# mainboard-gsm.net
KiCad netlist of a schematic drawn in EAGLE
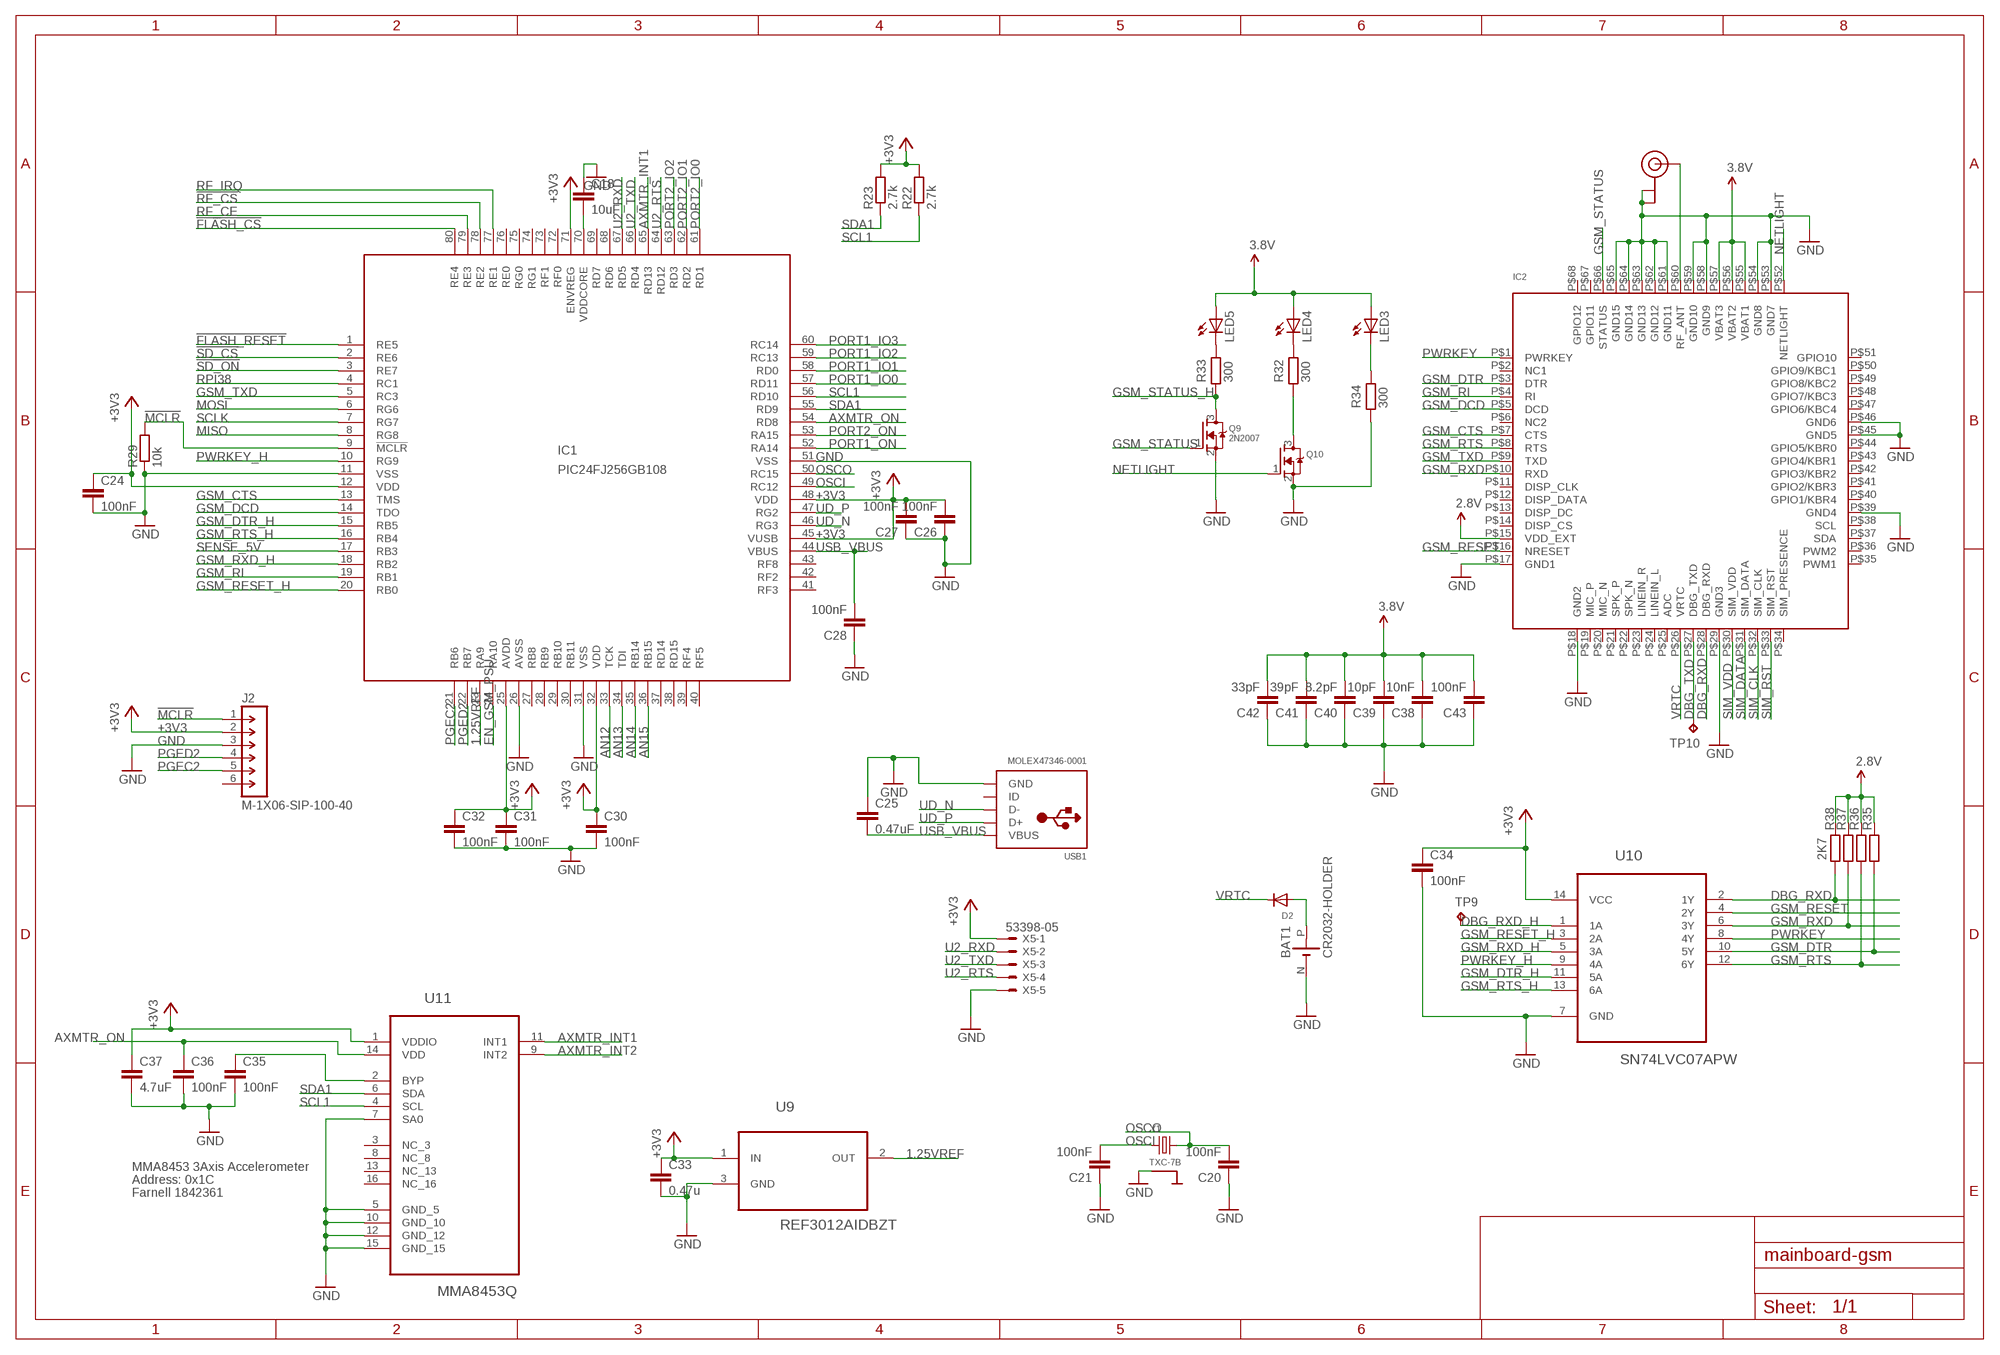
[diagram p0: schematic, sheet 1, part 1 of 3]
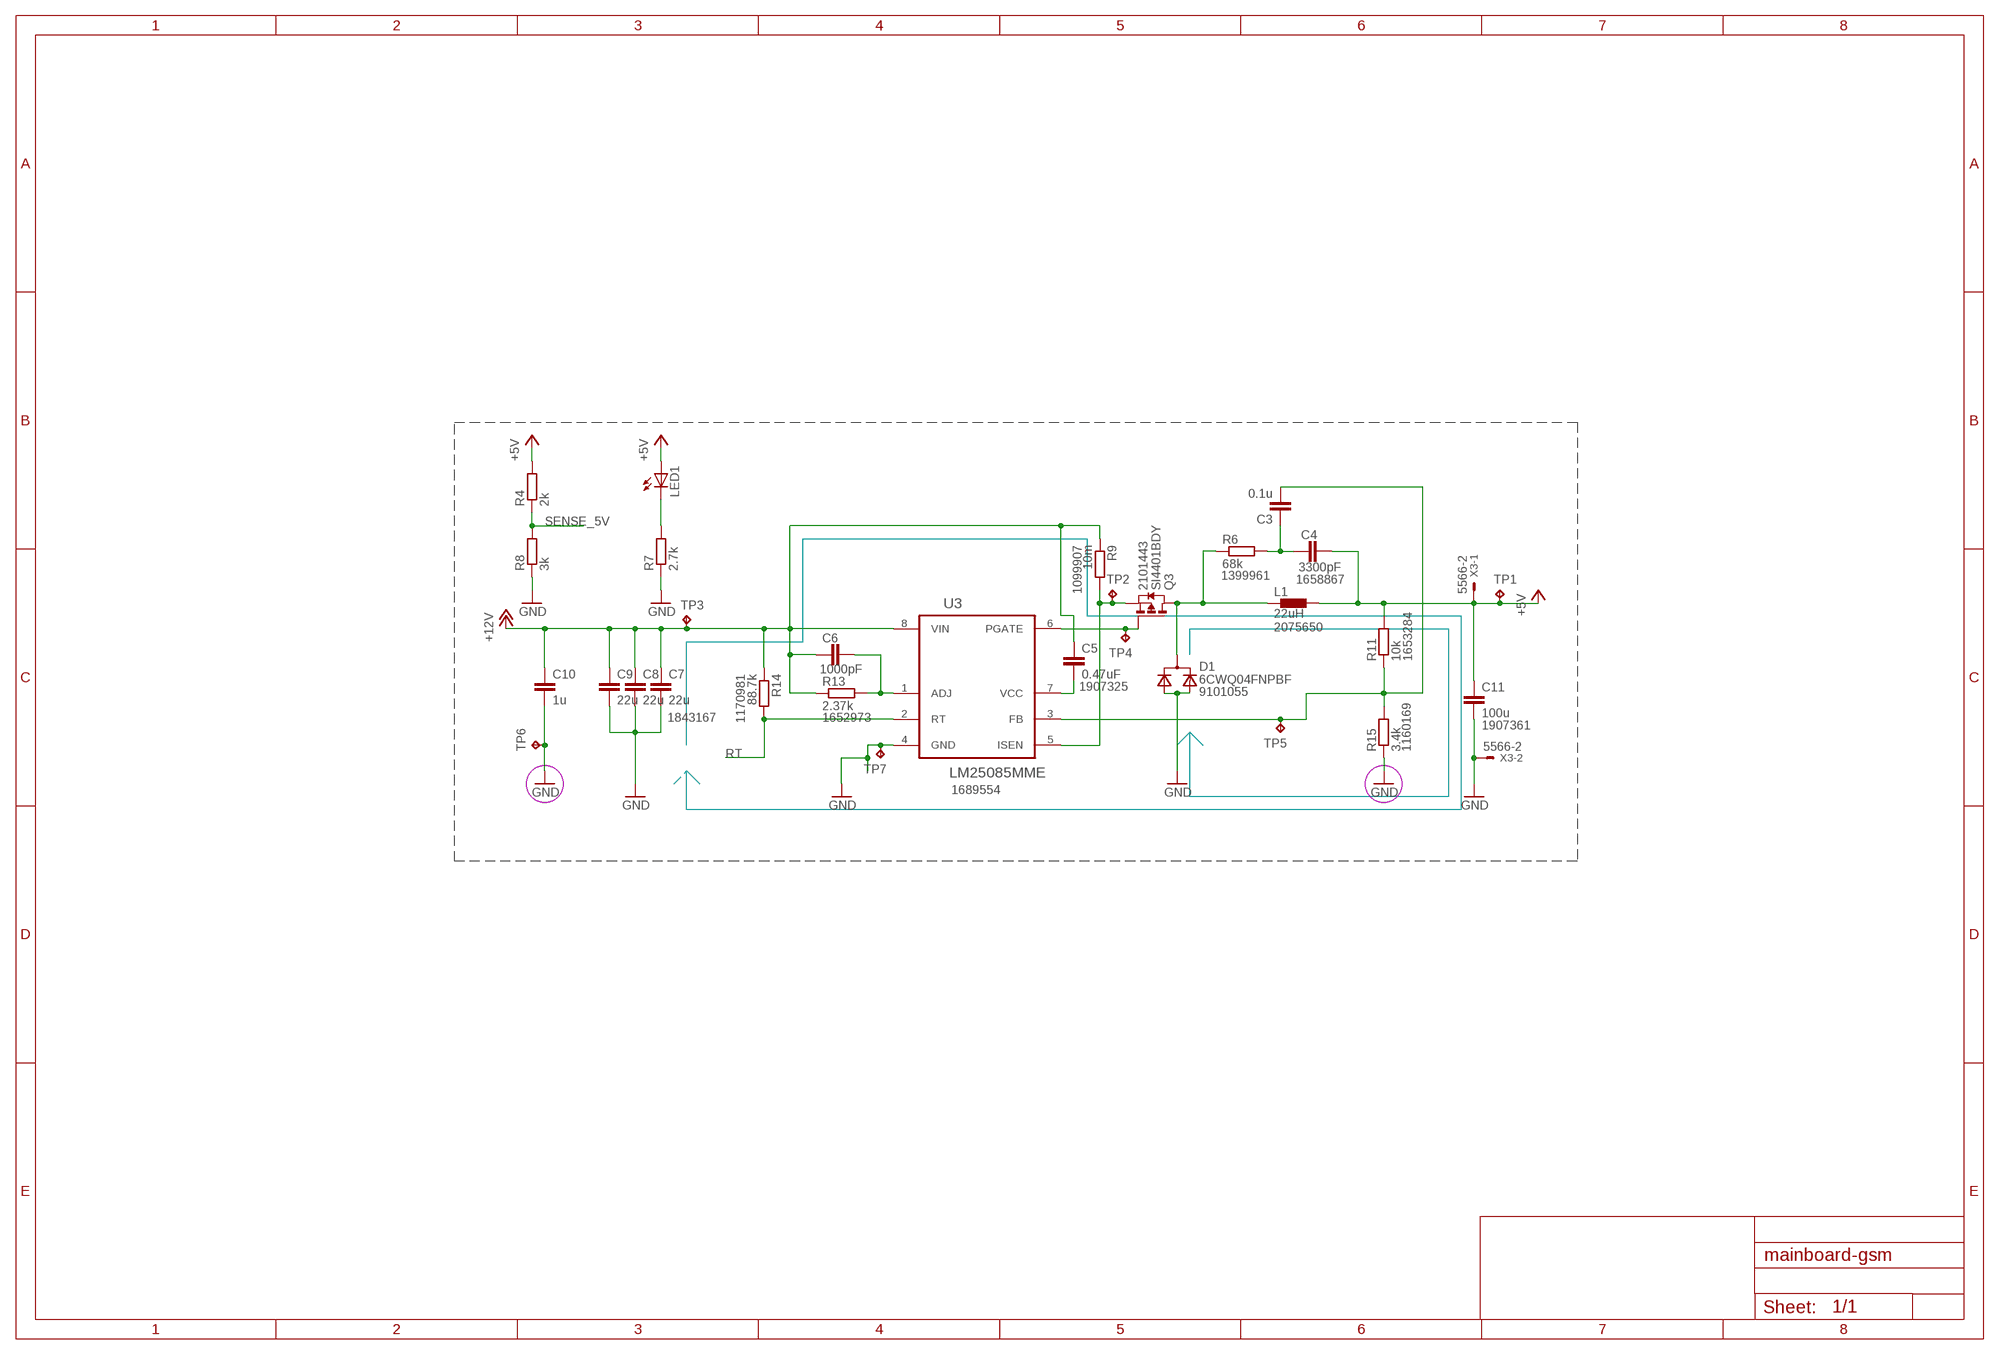
[diagram p1: schematic, sheet 1, part 2 of 3]
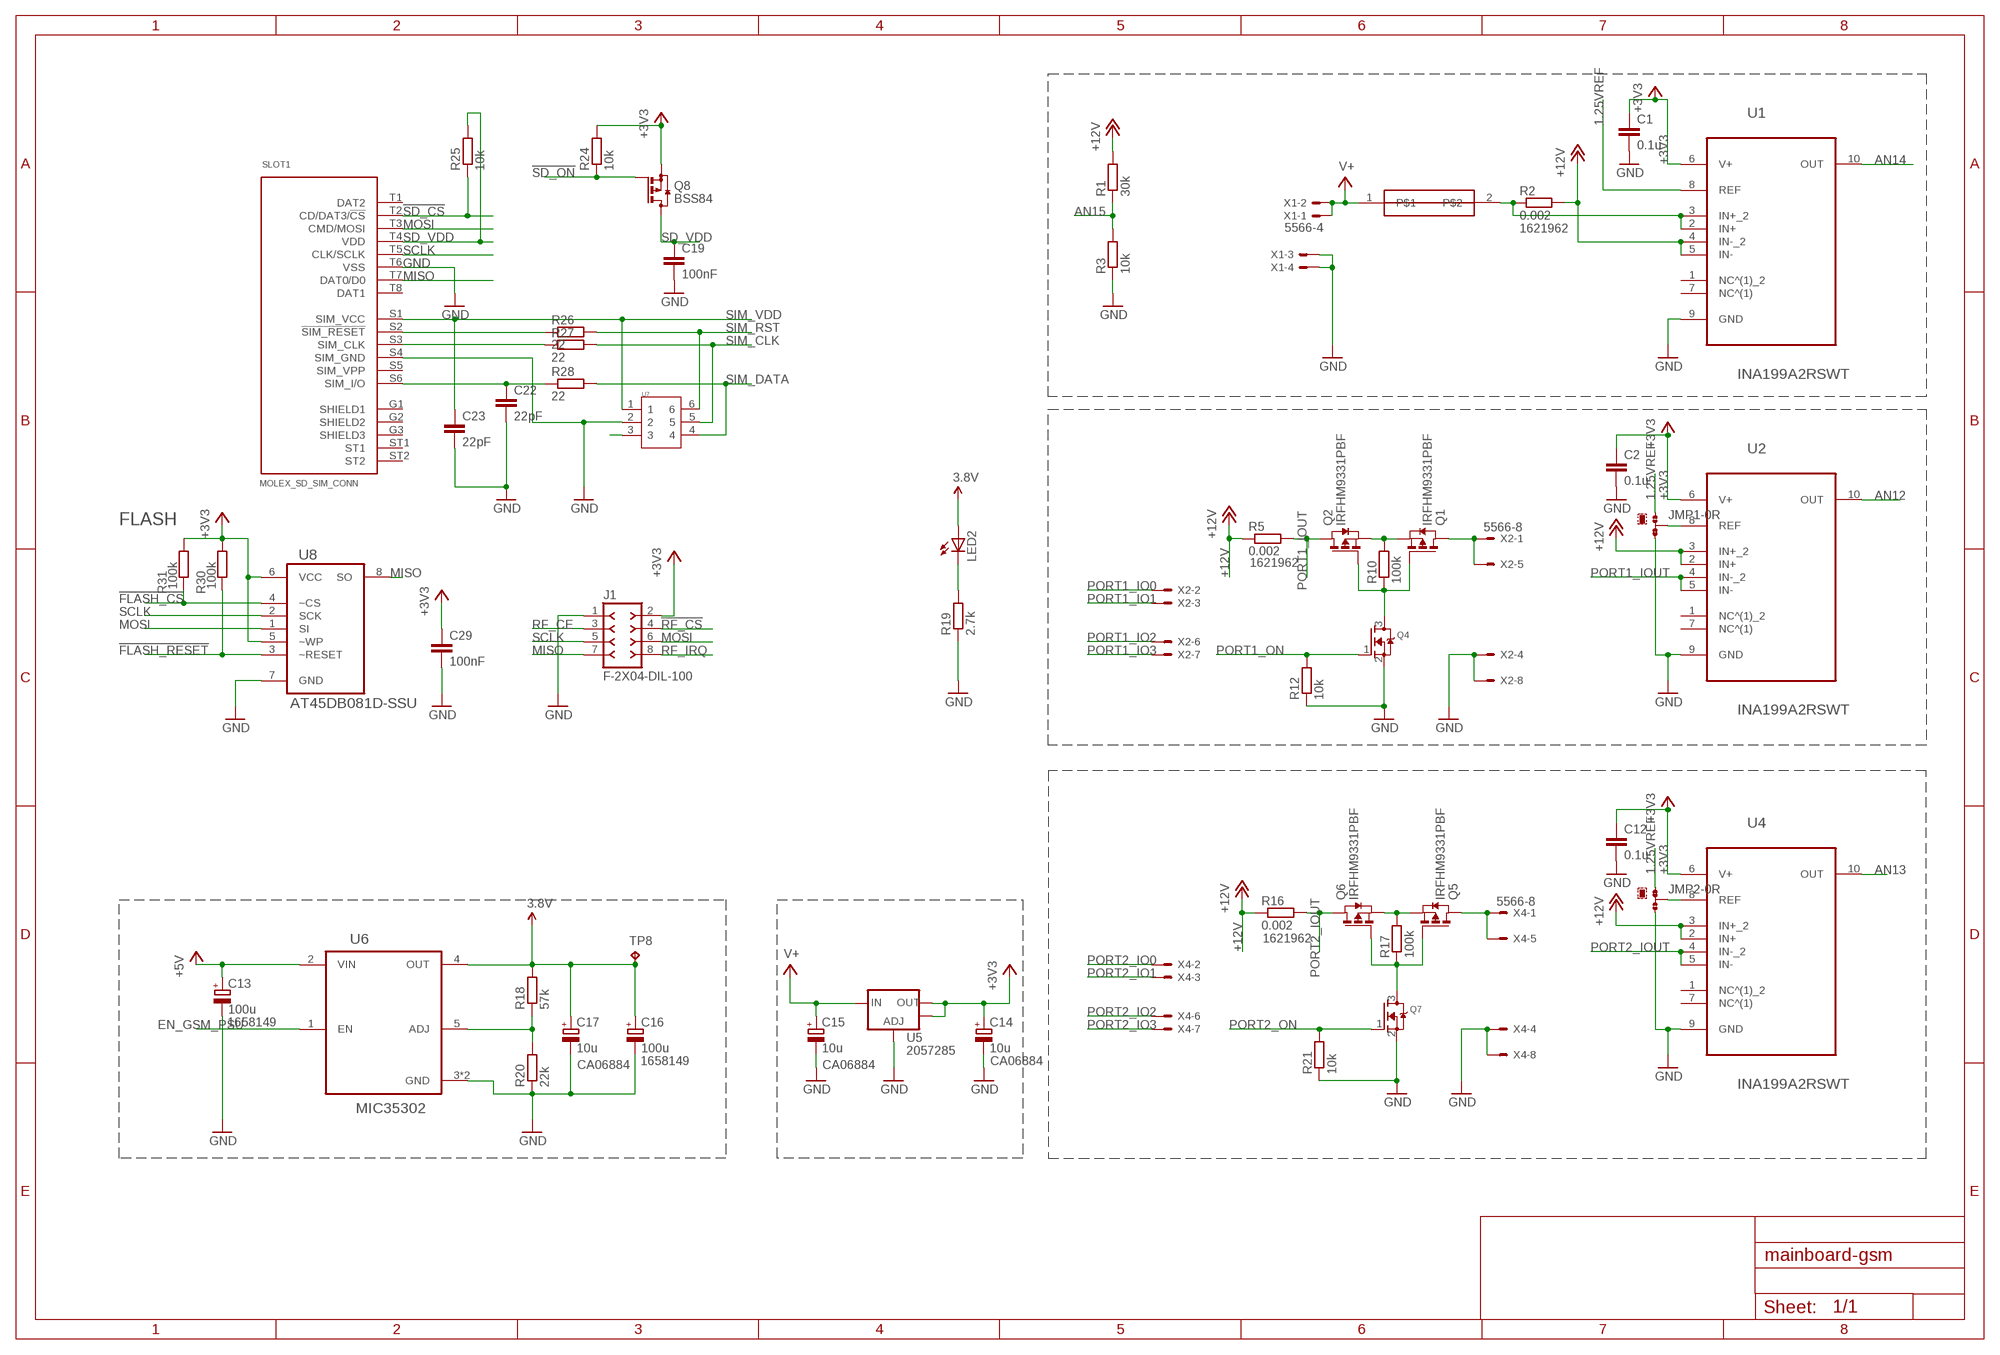
[diagram p2: schematic, sheet 1, part 3 of 3]

(export (version "E")
  (design (tool "Eeschema 10.0.6"))
  (components
    (comp (ref "ANT1")
      (value "U.FL")
      (footprint "eagle-import:U.FL")
      (libsource (lib "eagle-import") (part "U.FL"))
    )
    (comp (ref "BAT1")
      (value "CR2032-HOLDER")
      (footprint "eagle-import:CH28-2032L")
      (libsource (lib "eagle-import") (part "CR2032-HOLDER"))
    )
    (comp (ref "C1")
      (value "0.1u")
      (footprint "eagle-import:C0603")
      (libsource (lib "eagle-import") (part "C-EUC0603"))
    )
    (comp (ref "C2")
      (value "0.1u")
      (footprint "eagle-import:C0603")
      (libsource (lib "eagle-import") (part "C-EUC0603"))
    )
    (comp (ref "C3")
      (value "0.1u")
      (footprint "eagle-import:C0603")
      (libsource (lib "eagle-import") (part "C-EUC0603"))
    )
    (comp (ref "C4")
      (value "3300pF")
      (footprint "eagle-import:C0603")
      (fields (field (name "FARNELL") "1658867"))
      (libsource (lib "eagle-import") (part "C-EUC0603"))
    )
    (comp (ref "C5")
      (value "0.47uF")
      (footprint "eagle-import:C0805")
      (fields (field (name "FARNELL") "1907325"))
      (libsource (lib "eagle-import") (part "C-EUC0805"))
    )
    (comp (ref "C6")
      (value "1000pF")
      (footprint "eagle-import:C0603")
      (libsource (lib "eagle-import") (part "C-EUC0603"))
    )
    (comp (ref "C7")
      (value "22u")
      (footprint "eagle-import:C1812")
      (fields (field (name "FARNELL") "1843167"))
      (libsource (lib "eagle-import") (part "C-EUC1812"))
    )
    (comp (ref "C8")
      (value "22u")
      (footprint "eagle-import:C1812")
      (libsource (lib "eagle-import") (part "C-EUC1812"))
    )
    (comp (ref "C9")
      (value "22u")
      (footprint "eagle-import:C1812")
      (libsource (lib "eagle-import") (part "C-EUC1812"))
    )
    (comp (ref "C10")
      (value "1u")
      (footprint "eagle-import:C0805")
      (libsource (lib "eagle-import") (part "C-EUC0805"))
    )
    (comp (ref "C11")
      (value "100u")
      (footprint "eagle-import:C1210")
      (fields (field (name "FARNELL") "1907361"))
      (libsource (lib "eagle-import") (part "C-EUC1210"))
    )
    (comp (ref "C12")
      (value "0.1u")
      (footprint "eagle-import:C0603")
      (libsource (lib "eagle-import") (part "C-EUC0603"))
    )
    (comp (ref "C13")
      (value "100u")
      (footprint "eagle-import:B_3528-21R")
      (fields (field (name "FARNELL") "1658149"))
      (libsource (lib "eagle-import") (part "CPOL-EUB/3528-21R"))
    )
    (comp (ref "C14")
      (value "10u")
      (footprint "eagle-import:D_7343-31R")
      (fields (field (name "FARNELL") "CA06884"))
      (libsource (lib "eagle-import") (part "CPOL-EUD/7343-31R"))
    )
    (comp (ref "C15")
      (value "10u")
      (footprint "eagle-import:D_7343-31R")
      (fields (field (name "FARNELL") "CA06884"))
      (libsource (lib "eagle-import") (part "CPOL-EUD/7343-31R"))
    )
    (comp (ref "C16")
      (value "100u")
      (footprint "eagle-import:B_3528-21R")
      (fields (field (name "FARNELL") "1658149"))
      (libsource (lib "eagle-import") (part "CPOL-EUB/3528-21R"))
    )
    (comp (ref "C17")
      (value "10u")
      (footprint "eagle-import:D_7343-31R")
      (fields (field (name "FARNELL") "CA06884"))
      (libsource (lib "eagle-import") (part "CPOL-EUD/7343-31R"))
    )
    (comp (ref "C18")
      (value "10uF")
      (footprint "eagle-import:C0805")
      (libsource (lib "eagle-import") (part "C-EUC0805"))
    )
    (comp (ref "C19")
      (value "100nF")
      (footprint "eagle-import:C0603")
      (libsource (lib "eagle-import") (part "C-EUC0603"))
    )
    (comp (ref "C20")
      (value "100nF")
      (footprint "eagle-import:C0603")
      (libsource (lib "eagle-import") (part "C-EUC0603"))
    )
    (comp (ref "C21")
      (value "100nF")
      (footprint "eagle-import:C0603")
      (libsource (lib "eagle-import") (part "C-EUC0603"))
    )
    (comp (ref "C22")
      (value "22pF")
      (footprint "eagle-import:C0603")
      (libsource (lib "eagle-import") (part "C-EUC0603"))
    )
    (comp (ref "C23")
      (value "22pF")
      (footprint "eagle-import:C0603")
      (libsource (lib "eagle-import") (part "C-EUC0603"))
    )
    (comp (ref "C24")
      (value "100nF")
      (footprint "eagle-import:C0603")
      (libsource (lib "eagle-import") (part "C-EUC0603"))
    )
    (comp (ref "C25")
      (value "0.47uF")
      (footprint "eagle-import:C1206")
      (libsource (lib "eagle-import") (part "C-EUC1206"))
    )
    (comp (ref "C26")
      (value "100nF")
      (footprint "eagle-import:C0603")
      (libsource (lib "eagle-import") (part "C-EUC0603"))
    )
    (comp (ref "C27")
      (value "100nF")
      (footprint "eagle-import:C0603")
      (libsource (lib "eagle-import") (part "C-EUC0603"))
    )
    (comp (ref "C28")
      (value "100nF")
      (footprint "eagle-import:C0603")
      (libsource (lib "eagle-import") (part "C-EUC0603"))
    )
    (comp (ref "C29")
      (value "100nF")
      (footprint "eagle-import:C0603")
      (libsource (lib "eagle-import") (part "C-EUC0603"))
    )
    (comp (ref "C30")
      (value "100nF")
      (footprint "eagle-import:C0603")
      (libsource (lib "eagle-import") (part "C-EUC0603"))
    )
    (comp (ref "C31")
      (value "100nF")
      (footprint "eagle-import:C0603")
      (libsource (lib "eagle-import") (part "C-EUC0603"))
    )
    (comp (ref "C32")
      (value "100nF")
      (footprint "eagle-import:C0603")
      (libsource (lib "eagle-import") (part "C-EUC0603"))
    )
    (comp (ref "C33")
      (value "0.47u")
      (footprint "eagle-import:C0805")
      (libsource (lib "eagle-import") (part "C-EUC0805"))
    )
    (comp (ref "C34")
      (value "100nF")
      (footprint "eagle-import:C0603")
      (libsource (lib "eagle-import") (part "C-EUC0603"))
    )
    (comp (ref "C35")
      (value "100nF")
      (footprint "eagle-import:C0603")
      (libsource (lib "eagle-import") (part "C-EUC0603"))
    )
    (comp (ref "C36")
      (value "100nF")
      (footprint "eagle-import:C0603")
      (libsource (lib "eagle-import") (part "C-EUC0603"))
    )
    (comp (ref "C37")
      (value "4.7uF")
      (footprint "eagle-import:C0805")
      (libsource (lib "eagle-import") (part "C-EUC0805"))
    )
    (comp (ref "C38")
      (value "10nF")
      (footprint "eagle-import:C0603")
      (libsource (lib "eagle-import") (part "C-EUC0603"))
    )
    (comp (ref "C39")
      (value "10pF")
      (footprint "eagle-import:C0603")
      (libsource (lib "eagle-import") (part "C-EUC0603"))
    )
    (comp (ref "C40")
      (value "8.2pF")
      (footprint "eagle-import:C0603")
      (libsource (lib "eagle-import") (part "C-EUC0603"))
    )
    (comp (ref "C41")
      (value "39pF")
      (footprint "eagle-import:C0603")
      (libsource (lib "eagle-import") (part "C-EUC0603"))
    )
    (comp (ref "C42")
      (value "33pF")
      (footprint "eagle-import:C0603")
      (libsource (lib "eagle-import") (part "C-EUC0603"))
    )
    (comp (ref "C43")
      (value "100nF")
      (footprint "eagle-import:C0603")
      (libsource (lib "eagle-import") (part "C-EUC0603"))
    )
    (comp (ref "CONN1")
      (value "MINIBLADE_SOCKET")
      (footprint "eagle-import:LTF153008")
      (libsource (lib "eagle-import") (part "MINIBLADE_SOCKET"))
    )
    (comp (ref "D1")
      (value "6CWQ04FNPBF")
      (footprint "eagle-import:TO252-AA")
      (fields (field (name "FARNELL") "9101055"))
      (libsource (lib "eagle-import") (part "6CWQ04FNPBF"))
    )
    (comp (ref "D2")
      (value "DIODESOD-123")
      (footprint "eagle-import:SOD-123")
      (libsource (lib "eagle-import") (part "DIODESOD-123"))
    )
    (comp (ref "IC1")
      (value "PIC24FJ256GB108")
      (footprint "eagle-import:TQFP80-12X12")
      (fields
        (field (name "MPN") "PIC24FJ256GB108-I/PT")
        (field (name "MPN_1") "PIC24FJ256GB108-I/PT")
        (field (name "OC_FARNELL") "1576869")
        (field (name "OC_NEWARK") "54M5131")
      )
      (libsource (lib "eagle-import") (part "PIC24FJ256GB108"))
    )
    (comp (ref "IC2")
      (value "SIM900_LITERAL")
      (footprint "eagle-import:SIM900_SMT")
      (libsource (lib "eagle-import") (part "SIM900_LITERAL"))
    )
    (comp (ref "J1")
      (value "F-2X04-DIL-100")
      (footprint "eagle-import:DIL-100-2X04")
      (libsource (lib "eagle-import") (part "F-2X04-DIL-100"))
    )
    (comp (ref "J2")
      (value "M-1X06-SIP-100-40")
      (footprint "eagle-import:SIP-100-06-40")
      (libsource (lib "eagle-import") (part "M-1X06-SIP-100-40"))
    )
    (comp (ref "JMP1")
      (value "0R-JUMPA")
      (footprint "eagle-import:A0R-JMP")
      (libsource (lib "eagle-import") (part "0R-JUMPA"))
    )
    (comp (ref "JMP2")
      (value "0R-JUMPA")
      (footprint "eagle-import:A0R-JMP")
      (libsource (lib "eagle-import") (part "0R-JUMPA"))
    )
    (comp (ref "L1")
      (value "22uH")
      (footprint "eagle-import:HC9-XXX-R")
      (fields (field (name "FARNELL") "2075650"))
      (libsource (lib "eagle-import") (part "HC9-XXX-R"))
    )
    (comp (ref "LED1")
      (value "LEDCHIPLED_0805")
      (footprint "eagle-import:CHIPLED_0805")
      (libsource (lib "eagle-import") (part "LEDCHIPLED_0805"))
    )
    (comp (ref "LED2")
      (value "LEDCHIPLED_0805")
      (footprint "eagle-import:CHIPLED_0805")
      (libsource (lib "eagle-import") (part "LEDCHIPLED_0805"))
    )
    (comp (ref "LED3")
      (value "LEDCHIPLED_0805")
      (footprint "eagle-import:CHIPLED_0805")
      (libsource (lib "eagle-import") (part "LEDCHIPLED_0805"))
    )
    (comp (ref "LED4")
      (value "LEDCHIPLED_0805")
      (footprint "eagle-import:CHIPLED_0805")
      (libsource (lib "eagle-import") (part "LEDCHIPLED_0805"))
    )
    (comp (ref "LED5")
      (value "LEDCHIPLED_0805")
      (footprint "eagle-import:CHIPLED_0805")
      (libsource (lib "eagle-import") (part "LEDCHIPLED_0805"))
    )
    (comp (ref "Q1")
      (value "IRFHM9331PBF")
      (footprint "eagle-import:IR_PQFN_FET")
      (libsource (lib "eagle-import") (part "IRFHM9331PBF"))
    )
    (comp (ref "Q2")
      (value "IRFHM9331PBF")
      (footprint "eagle-import:IR_PQFN_FET")
      (libsource (lib "eagle-import") (part "IRFHM9331PBF"))
    )
    (comp (ref "Q3")
      (value "SI4401BDY")
      (footprint "eagle-import:SO8-FET")
      (fields (field (name "FARNELL") "2101443"))
      (libsource (lib "eagle-import") (part "SI4401BDY"))
    )
    (comp (ref "Q4")
      (value "MOSFET-NREFLOW")
      (footprint "eagle-import:SOT23")
      (libsource (lib "eagle-import") (part "MOSFET-NREFLOW"))
    )
    (comp (ref "Q5")
      (value "IRFHM9331PBF")
      (footprint "eagle-import:IR_PQFN_FET")
      (libsource (lib "eagle-import") (part "IRFHM9331PBF"))
    )
    (comp (ref "Q6")
      (value "IRFHM9331PBF")
      (footprint "eagle-import:IR_PQFN_FET")
      (libsource (lib "eagle-import") (part "IRFHM9331PBF"))
    )
    (comp (ref "Q7")
      (value "MOSFET-NREFLOW")
      (footprint "eagle-import:SOT23")
      (libsource (lib "eagle-import") (part "MOSFET-NREFLOW"))
    )
    (comp (ref "Q8")
      (value "BSS84")
      (footprint "eagle-import:SOT23")
      (libsource (lib "eagle-import") (part "BSS84"))
    )
    (comp (ref "Q9")
      (value "2N2007")
      (footprint "eagle-import:SOT23")
      (libsource (lib "eagle-import") (part "MOSFET-NREFLOW"))
    )
    (comp (ref "Q10")
      (value "MOSFET-NREFLOW")
      (footprint "eagle-import:SOT23")
      (libsource (lib "eagle-import") (part "MOSFET-NREFLOW"))
    )
    (comp (ref "R1")
      (value "30k")
      (footprint "eagle-import:R0805")
      (libsource (lib "eagle-import") (part "R-EU_R0805"))
    )
    (comp (ref "R2")
      (value "0.002")
      (footprint "eagle-import:R1206")
      (fields (field (name "FARNELL") "1621962"))
      (libsource (lib "eagle-import") (part "R-EU_R1206"))
    )
    (comp (ref "R3")
      (value "10k")
      (footprint "eagle-import:R0805")
      (libsource (lib "eagle-import") (part "R-EU_R0805"))
    )
    (comp (ref "R4")
      (value "2k")
      (footprint "eagle-import:R0805")
      (libsource (lib "eagle-import") (part "R-EU_R0805"))
    )
    (comp (ref "R5")
      (value "0.002")
      (footprint "eagle-import:R1206")
      (fields (field (name "FARNELL") "1621962"))
      (libsource (lib "eagle-import") (part "R-EU_R1206"))
    )
    (comp (ref "R6")
      (value "68k")
      (footprint "eagle-import:R0603")
      (fields (field (name "FARNELL") "1399961"))
      (libsource (lib "eagle-import") (part "R-EU_R0603"))
    )
    (comp (ref "R7")
      (value "2.7k")
      (footprint "eagle-import:R0805")
      (libsource (lib "eagle-import") (part "R-EU_R0805"))
    )
    (comp (ref "R8")
      (value "3k")
      (footprint "eagle-import:R0805")
      (libsource (lib "eagle-import") (part "R-EU_R0805"))
    )
    (comp (ref "R9")
      (value "10m")
      (footprint "eagle-import:R1206")
      (fields (field (name "FARNELL") "1099907"))
      (libsource (lib "eagle-import") (part "R-EU_R1206"))
    )
    (comp (ref "R10")
      (value "100k")
      (footprint "eagle-import:R0603")
      (libsource (lib "eagle-import") (part "R-EU_R0603"))
    )
    (comp (ref "R11")
      (value "10k")
      (footprint "eagle-import:R0805")
      (fields (field (name "FARNELL") "1653284"))
      (libsource (lib "eagle-import") (part "R-EU_R0805"))
    )
    (comp (ref "R12")
      (value "10k")
      (footprint "eagle-import:R0603")
      (libsource (lib "eagle-import") (part "R-EU_R0603"))
    )
    (comp (ref "R13")
      (value "2.37k")
      (footprint "eagle-import:R0805")
      (fields (field (name "FARNELL") "1652973"))
      (libsource (lib "eagle-import") (part "R-EU_R0805"))
    )
    (comp (ref "R14")
      (value "88.7k")
      (footprint "eagle-import:R0603")
      (fields (field (name "FARNELL") "1170981"))
      (libsource (lib "eagle-import") (part "R-EU_R0603"))
    )
    (comp (ref "R15")
      (value "3.4k")
      (footprint "eagle-import:R0805")
      (fields (field (name "FARNELL") "1160169"))
      (libsource (lib "eagle-import") (part "R-EU_R0805"))
    )
    (comp (ref "R16")
      (value "0.002")
      (footprint "eagle-import:R1206")
      (fields (field (name "FARNELL") "1621962"))
      (libsource (lib "eagle-import") (part "R-EU_R1206"))
    )
    (comp (ref "R17")
      (value "100k")
      (footprint "eagle-import:R0603")
      (libsource (lib "eagle-import") (part "R-EU_R0603"))
    )
    (comp (ref "R18")
      (value "57k")
      (footprint "eagle-import:R0603")
      (libsource (lib "eagle-import") (part "R-EU_R0603"))
    )
    (comp (ref "R19")
      (value "2.7k")
      (footprint "eagle-import:R0805")
      (libsource (lib "eagle-import") (part "R-EU_R0805"))
    )
    (comp (ref "R20")
      (value "22k")
      (footprint "eagle-import:R0603")
      (libsource (lib "eagle-import") (part "R-EU_R0603"))
    )
    (comp (ref "R21")
      (value "10k")
      (footprint "eagle-import:R0603")
      (libsource (lib "eagle-import") (part "R-EU_R0603"))
    )
    (comp (ref "R22")
      (value "2.7k")
      (footprint "eagle-import:R0603")
      (libsource (lib "eagle-import") (part "R-EU_R0603"))
    )
    (comp (ref "R23")
      (value "2.7k")
      (footprint "eagle-import:R0603")
      (libsource (lib "eagle-import") (part "R-EU_R0603"))
    )
    (comp (ref "R24")
      (value "10k")
      (footprint "eagle-import:R0603")
      (libsource (lib "eagle-import") (part "R-EU_R0603"))
    )
    (comp (ref "R25")
      (value "10k")
      (footprint "eagle-import:R0603")
      (libsource (lib "eagle-import") (part "R-EU_R0603"))
    )
    (comp (ref "R26")
      (value "22")
      (footprint "eagle-import:R0603")
      (libsource (lib "eagle-import") (part "R-EU_R0603"))
    )
    (comp (ref "R27")
      (value "22")
      (footprint "eagle-import:R0603")
      (libsource (lib "eagle-import") (part "R-EU_R0603"))
    )
    (comp (ref "R28")
      (value "22")
      (footprint "eagle-import:R0603")
      (libsource (lib "eagle-import") (part "R-EU_R0603"))
    )
    (comp (ref "R29")
      (value "10k")
      (footprint "eagle-import:R0603")
      (libsource (lib "eagle-import") (part "R-EU_R0603"))
    )
    (comp (ref "R30")
      (value "100k")
      (footprint "eagle-import:R0603")
      (libsource (lib "eagle-import") (part "R-EU_R0603"))
    )
    (comp (ref "R31")
      (value "100k")
      (footprint "eagle-import:R0603")
      (libsource (lib "eagle-import") (part "R-EU_R0603"))
    )
    (comp (ref "R32")
      (value "300")
      (footprint "eagle-import:R0603")
      (libsource (lib "eagle-import") (part "R-EU_R0603"))
    )
    (comp (ref "R33")
      (value "300")
      (footprint "eagle-import:R0603")
      (libsource (lib "eagle-import") (part "R-EU_R0603"))
    )
    (comp (ref "R34")
      (value "300")
      (footprint "eagle-import:R0603")
      (libsource (lib "eagle-import") (part "R-EU_R0603"))
    )
    (comp (ref "R35")
      (value "2K7")
      (footprint "eagle-import:R0603")
      (libsource (lib "eagle-import") (part "R-EU_R0603"))
    )
    (comp (ref "R36")
      (value "2K7")
      (footprint "eagle-import:R0603")
      (libsource (lib "eagle-import") (part "R-EU_R0603"))
    )
    (comp (ref "R37")
      (value "2K7")
      (footprint "eagle-import:R0603")
      (libsource (lib "eagle-import") (part "R-EU_R0603"))
    )
    (comp (ref "R38")
      (value "2K7")
      (footprint "eagle-import:R0603")
      (libsource (lib "eagle-import") (part "R-EU_R0603"))
    )
    (comp (ref "SLOT1")
      (value "MOLEX_SD_SIM_CONN")
      (footprint "eagle-import:MOLEX_SDSIM_COMBO")
      (libsource (lib "eagle-import") (part "MOLEX_SD_SIM_CONN"))
    )
    (comp (ref "TP1")
      (value "TPTP09R")
      (footprint "eagle-import:TP09R")
      (libsource (lib "eagle-import") (part "TPTP09R"))
    )
    (comp (ref "TP2")
      (value "TPTP10R")
      (footprint "eagle-import:TP10R")
      (libsource (lib "eagle-import") (part "TPTP10R"))
    )
    (comp (ref "TP3")
      (value "TPTP10R")
      (footprint "eagle-import:TP10R")
      (libsource (lib "eagle-import") (part "TPTP10R"))
    )
    (comp (ref "TP4")
      (value "TPTP10R")
      (footprint "eagle-import:TP10R")
      (libsource (lib "eagle-import") (part "TPTP10R"))
    )
    (comp (ref "TP5")
      (value "TPTP10R")
      (footprint "eagle-import:TP10R")
      (libsource (lib "eagle-import") (part "TPTP10R"))
    )
    (comp (ref "TP6")
      (value "TPTP10R")
      (footprint "eagle-import:TP10R")
      (libsource (lib "eagle-import") (part "TPTP10R"))
    )
    (comp (ref "TP7")
      (value "TPTP10R")
      (footprint "eagle-import:TP10R")
      (libsource (lib "eagle-import") (part "TPTP10R"))
    )
    (comp (ref "TP8")
      (value "TPTP09R")
      (footprint "eagle-import:TP09R")
      (libsource (lib "eagle-import") (part "TPTP09R"))
    )
    (comp (ref "TP9")
      (value "TPTP10R")
      (footprint "eagle-import:TP10R")
      (libsource (lib "eagle-import") (part "TPTP10R"))
    )
    (comp (ref "TP10")
      (value "TPTP10R")
      (footprint "eagle-import:TP10R")
      (libsource (lib "eagle-import") (part "TPTP10R"))
    )
    (comp (ref "U1")
      (value "INA199A2RSWT")
      (footprint "eagle-import:QFN40P140X180X55-10N")
      (fields
        (field (name "MPN") "INA199A2RSWT")
        (field (name "OC_FARNELL") "1815789")
        (field (name "OC_NEWARK") "74R0562")
        (field (name "PACKAGE") "UQFN-10")
        (field (name "SUPPLIER") "Texas Instrument")
      )
      (libsource (lib "eagle-import") (part "INA199A2RSWT"))
    )
    (comp (ref "U2")
      (value "INA199A2RSWT")
      (footprint "eagle-import:QFN40P140X180X55-10N")
      (libsource (lib "eagle-import") (part "INA199A2RSWT"))
    )
    (comp (ref "U3")
      (value "LM25085MME")
      (footprint "eagle-import:MINI-SO8")
      (fields (field (name "FARNELL") "1689554"))
      (libsource (lib "eagle-import") (part "LM25085MME"))
    )
    (comp (ref "U4")
      (value "INA199A2RSWT")
      (footprint "eagle-import:QFN40P140X180X55-10N")
      (libsource (lib "eagle-import") (part "INA199A2RSWT"))
    )
    (comp (ref "U5")
      (value "V_REG_LM1117SOT223")
      (footprint "eagle-import:SOT223")
      (fields (field (name "FARNELL") "2057285"))
      (libsource (lib "eagle-import") (part "V_REG_LM1117SOT223"))
    )
    (comp (ref "U6")
      (value "MIC35302")
      (footprint "eagle-import:TO252-5")
      (libsource (lib "eagle-import") (part "MIC35302"))
    )
    (comp (ref "U7")
      (value "SMF05C'-SC70'")
      (footprint "eagle-import:SC70-6L")
      (libsource (lib "eagle-import") (part "SMF05C'-SC70'"))
    )
    (comp (ref "U8")
      (value "AT45DB081D-SSU")
      (footprint "eagle-import:SOIC127P600X175-8N")
      (libsource (lib "eagle-import") (part "AT45DB081D-SSU"))
    )
    (comp (ref "U9")
      (value "REF3012AIDBZT")
      (footprint "eagle-import:SOT95P237X112-3N")
      (fields (field (name "MPN") "REF3120AIDBZT"))
      (libsource (lib "eagle-import") (part "REF3012AIDBZT"))
    )
    (comp (ref "U10")
      (value "SN74LVC07APW")
      (footprint "eagle-import:SOP65P640X120-14N")
      (libsource (lib "eagle-import") (part "SN74LVC07APW"))
    )
    (comp (ref "U11")
      (value "MMA8453Q")
      (footprint "eagle-import:QFN50P300X300X100-16N")
      (libsource (lib "eagle-import") (part "MMA8453Q"))
    )
    (comp (ref "USB1")
      (value "MOLEX47346-0001")
      (footprint "eagle-import:47346-0001")
      (libsource (lib "eagle-import") (part "MOLEX47346-0001"))
    )
    (comp (ref "X1")
      (value "5566-4")
      (footprint "eagle-import:5566-4")
      (libsource (lib "eagle-import") (part "5566-4"))
    )
    (comp (ref "X2")
      (value "5566-8")
      (footprint "eagle-import:5566-8")
      (libsource (lib "eagle-import") (part "5566-8"))
    )
    (comp (ref "X3")
      (value "5566-2")
      (footprint "eagle-import:5566-2")
      (libsource (lib "eagle-import") (part "5566-2"))
    )
    (comp (ref "X4")
      (value "5566-8")
      (footprint "eagle-import:5566-8")
      (libsource (lib "eagle-import") (part "5566-8"))
    )
    (comp (ref "X5")
      (value "53398-05")
      (footprint "eagle-import:53398-05")
      (libsource (lib "eagle-import") (part "53?-05398"))
    )
    (comp (ref "Y1")
      (value "TXC-7B")
      (footprint "eagle-import:TXC-7B")
      (libsource (lib "eagle-import") (part "TXC-7B"))
    )
  )
  (nets
    (net (code "1") (name "+3V3") (class "Default")
      (node (ref "C1") (pin "1") (pinfunction "1_1") (pintype "passive"))
      (node (ref "C12") (pin "1") (pinfunction "1_1") (pintype "passive"))
      (node (ref "C14") (pin "+") (pinfunction "+_+") (pintype "passive"))
      (node (ref "C2") (pin "1") (pinfunction "1_1") (pintype "passive"))
      (node (ref "C24") (pin "1") (pinfunction "1_1") (pintype "passive"))
      (node (ref "C26") (pin "2") (pinfunction "2_2") (pintype "passive"))
      (node (ref "C27") (pin "2") (pinfunction "2_2") (pintype "passive"))
      (node (ref "C29") (pin "1") (pinfunction "1_1") (pintype "passive"))
      (node (ref "C30") (pin "1") (pinfunction "1_1") (pintype "passive"))
      (node (ref "C31") (pin "1") (pinfunction "1_1") (pintype "passive"))
      (node (ref "C32") (pin "1") (pinfunction "1_1") (pintype "passive"))
      (node (ref "C33") (pin "1") (pinfunction "1_1") (pintype "passive"))
      (node (ref "C34") (pin "1") (pinfunction "1_1") (pintype "passive"))
      (node (ref "C37") (pin "1") (pinfunction "1_1") (pintype "passive"))
      (node (ref "IC1") (pin "12") (pinfunction "VDD_12") (pintype "power_in"))
      (node (ref "IC1") (pin "25") (pinfunction "AVDD_25") (pintype "power_in"))
      (node (ref "IC1") (pin "32") (pinfunction "VDD_32") (pintype "power_in"))
      (node (ref "IC1") (pin "45") (pinfunction "VUSB_45") (pintype "passive"))
      (node (ref "IC1") (pin "48") (pinfunction "VDD_48") (pintype "power_in"))
      (node (ref "IC1") (pin "71") (pinfunction "ENVREG_71") (pintype "passive"))
      (node (ref "J1") (pin "2") (pinfunction "2_2") (pintype "passive"))
      (node (ref "J2") (pin "2") (pinfunction "2_2") (pintype "passive"))
      (node (ref "Q8") (pin "2") (pinfunction "S_2") (pintype "passive"))
      (node (ref "R22") (pin "2") (pinfunction "2_2") (pintype "passive"))
      (node (ref "R23") (pin "2") (pinfunction "2_2") (pintype "passive"))
      (node (ref "R24") (pin "2") (pinfunction "2_2") (pintype "passive"))
      (node (ref "R30") (pin "1") (pinfunction "1_1") (pintype "passive"))
      (node (ref "R31") (pin "1") (pinfunction "1_1") (pintype "passive"))
      (node (ref "U1") (pin "6") (pinfunction "V+_6") (pintype "power_in"))
      (node (ref "U10") (pin "14") (pinfunction "VCC_14") (pintype "power_in"))
      (node (ref "U11") (pin "1") (pinfunction "VDDIO_1") (pintype "power_in"))
      (node (ref "U2") (pin "6") (pinfunction "V+_6") (pintype "power_in"))
      (node (ref "U4") (pin "6") (pinfunction "V+_6") (pintype "power_in"))
      (node (ref "U5") (pin "2") (pinfunction "OUT_2") (pintype "output"))
      (node (ref "U5") (pin "4") (pinfunction "OUT_4") (pintype "output"))
      (node (ref "U8") (pin "5") (pinfunction "~{WP}_5") (pintype "input"))
      (node (ref "U8") (pin "6") (pinfunction "VCC_6") (pintype "power_in"))
      (node (ref "U9") (pin "1") (pinfunction "IN_1") (pintype "power_in"))
      (node (ref "X5") (pin "1") (pinfunction "S_1") (pintype "passive"))
    )
    (net (code "2") (name "+5V") (class "Default")
      (node (ref "C11") (pin "1") (pinfunction "1_1") (pintype "passive"))
      (node (ref "C13") (pin "+") (pinfunction "+_+") (pintype "passive"))
      (node (ref "C4") (pin "1") (pinfunction "1_1") (pintype "passive"))
      (node (ref "L1") (pin "2") (pinfunction "2_2") (pintype "passive"))
      (node (ref "LED1") (pin "A") (pinfunction "A_A") (pintype "passive"))
      (node (ref "R11") (pin "2") (pinfunction "2_2") (pintype "passive"))
      (node (ref "R4") (pin "2") (pinfunction "2_2") (pintype "passive"))
      (node (ref "TP1") (pin "TP") (pinfunction "TP_TP") (pintype "input"))
      (node (ref "U6") (pin "2") (pinfunction "VIN_2") (pintype "power_in"))
      (node (ref "X3") (pin "1") (pinfunction "S_1") (pintype "passive"))
    )
    (net (code "3") (name "+12V") (class "Default")
      (node (ref "C10") (pin "1") (pinfunction "1_1") (pintype "passive"))
      (node (ref "C5") (pin "1") (pinfunction "1_1") (pintype "passive"))
      (node (ref "C6") (pin "1") (pinfunction "1_1") (pintype "passive"))
      (node (ref "C7") (pin "1") (pinfunction "1_1") (pintype "passive"))
      (node (ref "C8") (pin "1") (pinfunction "1_1") (pintype "passive"))
      (node (ref "C9") (pin "1") (pinfunction "1_1") (pintype "passive"))
      (node (ref "R1") (pin "2") (pinfunction "2_2") (pintype "passive"))
      (node (ref "R13") (pin "1") (pinfunction "1_1") (pintype "passive"))
      (node (ref "R14") (pin "1") (pinfunction "1_1") (pintype "passive"))
      (node (ref "R16") (pin "1") (pinfunction "1_1") (pintype "passive"))
      (node (ref "R2") (pin "2") (pinfunction "2_2") (pintype "passive"))
      (node (ref "R5") (pin "1") (pinfunction "1_1") (pintype "passive"))
      (node (ref "R9") (pin "1") (pinfunction "1_1") (pintype "passive"))
      (node (ref "TP3") (pin "TP") (pinfunction "TP_TP") (pintype "input"))
      (node (ref "U1") (pin "4") (pinfunction "IN-_2_4") (pintype "input"))
      (node (ref "U1") (pin "5") (pinfunction "IN-_5") (pintype "input"))
      (node (ref "U2") (pin "2") (pinfunction "IN+_2") (pintype "input"))
      (node (ref "U2") (pin "3") (pinfunction "IN+_2_3") (pintype "input"))
      (node (ref "U3") (pin "8") (pinfunction "VIN_8") (pintype "power_in"))
      (node (ref "U4") (pin "2") (pinfunction "IN+_2") (pintype "input"))
      (node (ref "U4") (pin "3") (pinfunction "IN+_2_3") (pintype "input"))
    )
    (net (code "4") (name "/1.25VREF") (class "Default")
      (node (ref "IC1") (pin "23") (pinfunction "RA9_23") (pintype "bidirectional"))
      (node (ref "JMP1") (pin "1") (pinfunction "1_1") (pintype "passive"))
      (node (ref "JMP2") (pin "1") (pinfunction "1_1") (pintype "passive"))
      (node (ref "U1") (pin "8") (pinfunction "REF_8") (pintype "input"))
      (node (ref "U9") (pin "2") (pinfunction "OUT_2") (pintype "output"))
    )
    (net (code "5") (name "/AN12") (class "Default")
      (node (ref "IC1") (pin "33") (pinfunction "TCK_33") (pintype "input"))
      (node (ref "U2") (pin "10") (pinfunction "OUT_10") (pintype "output"))
    )
    (net (code "6") (name "/AN13") (class "Default")
      (node (ref "IC1") (pin "34") (pinfunction "TDI_34") (pintype "input"))
      (node (ref "U4") (pin "10") (pinfunction "OUT_10") (pintype "output"))
    )
    (net (code "7") (name "/AN14") (class "Default")
      (node (ref "IC1") (pin "35") (pinfunction "RB14_35") (pintype "bidirectional"))
      (node (ref "U1") (pin "10") (pinfunction "OUT_10") (pintype "output"))
    )
    (net (code "8") (name "/AN15") (class "Default")
      (node (ref "IC1") (pin "36") (pinfunction "RB15_36") (pintype "bidirectional"))
      (node (ref "R1") (pin "1") (pinfunction "1_1") (pintype "passive"))
      (node (ref "R3") (pin "2") (pinfunction "2_2") (pintype "passive"))
    )
    (net (code "9") (name "/AXMTR_INT1") (class "Default")
      (node (ref "IC1") (pin "65") (pinfunction "RD13_65") (pintype "bidirectional"))
      (node (ref "U11") (pin "11") (pinfunction "INT1_11") (pintype "output"))
    )
    (net (code "10") (name "/AXMTR_INT2") (class "Default")
      (node (ref "U11") (pin "9") (pinfunction "INT2_9") (pintype "output"))
    )
    (net (code "11") (name "/AXMTR_ON") (class "Default")
      (node (ref "C36") (pin "1") (pinfunction "1_1") (pintype "passive"))
      (node (ref "IC1") (pin "54") (pinfunction "RD8_54") (pintype "bidirectional"))
      (node (ref "U11") (pin "14") (pinfunction "VDD_14") (pintype "power_in"))
    )
    (net (code "12") (name "/DBG_RXD") (class "Default")
      (node (ref "IC2") (pin "P$28") (pinfunction "DBG_RXD_P$28") (pintype "input"))
      (node (ref "R38") (pin "1") (pinfunction "1_1") (pintype "passive"))
      (node (ref "U10") (pin "2") (pinfunction "1Y_2") (pintype "output"))
    )
    (net (code "13") (name "/DBG_RXD_H") (class "Default")
      (node (ref "TP9") (pin "TP") (pinfunction "TP_TP") (pintype "input"))
      (node (ref "U10") (pin "1") (pinfunction "1A_1") (pintype "input"))
    )
    (net (code "14") (name "/DBG_TXD") (class "Default")
      (node (ref "IC2") (pin "P$27") (pinfunction "DBG_TXD_P$27") (pintype "output"))
      (node (ref "TP10") (pin "TP") (pinfunction "TP_TP") (pintype "input"))
    )
    (net (code "15") (name "/EN_GSM_PSU") (class "Default")
      (node (ref "IC1") (pin "24") (pinfunction "RA10_24") (pintype "bidirectional"))
      (node (ref "U6") (pin "1") (pinfunction "EN_1") (pintype "input"))
    )
    (net (code "16") (name "/GPIO11") (class "Default")
      (node (ref "IC2") (pin "P$67") (pinfunction "GPIO11_P$67") (pintype "power_in"))
    )
    (net (code "17") (name "/GPIO12") (class "Default")
      (node (ref "IC2") (pin "P$68") (pinfunction "GPIO12_P$68") (pintype "power_in"))
    )
    (net (code "18") (name "/GSM_CTS") (class "Default")
      (node (ref "IC1") (pin "13") (pinfunction "TMS_13") (pintype "input"))
      (node (ref "IC2") (pin "P$7") (pinfunction "CTS_P$7") (pintype "output"))
    )
    (net (code "19") (name "/GSM_DCD") (class "Default")
      (node (ref "IC1") (pin "14") (pinfunction "TDO_14") (pintype "output"))
      (node (ref "IC2") (pin "P$5") (pinfunction "DCD_P$5") (pintype "output"))
    )
    (net (code "20") (name "/GSM_DTR") (class "Default")
      (node (ref "IC2") (pin "P$3") (pinfunction "DTR_P$3") (pintype "input"))
      (node (ref "R35") (pin "1") (pinfunction "1_1") (pintype "passive"))
      (node (ref "U10") (pin "10") (pinfunction "5Y_10") (pintype "output"))
    )
    (net (code "21") (name "/GSM_DTR_H") (class "Default")
      (node (ref "IC1") (pin "15") (pinfunction "RB5_15") (pintype "bidirectional"))
      (node (ref "U10") (pin "11") (pinfunction "5A_11") (pintype "input"))
    )
    (net (code "22") (name "/GSM_RESET") (class "Default")
      (node (ref "IC2") (pin "P$16") (pinfunction "NRESET_P$16") (pintype "bidirectional"))
      (node (ref "U10") (pin "4") (pinfunction "2Y_4") (pintype "output"))
    )
    (net (code "23") (name "/GSM_RESET_H") (class "Default")
      (node (ref "IC1") (pin "20") (pinfunction "RB0_20") (pintype "bidirectional"))
      (node (ref "U10") (pin "3") (pinfunction "2A_3") (pintype "input"))
    )
    (net (code "24") (name "/GSM_RI") (class "Default")
      (node (ref "IC1") (pin "19") (pinfunction "RB1_19") (pintype "bidirectional"))
      (node (ref "IC2") (pin "P$4") (pinfunction "RI_P$4") (pintype "output"))
    )
    (net (code "25") (name "/GSM_RTS") (class "Default")
      (node (ref "IC2") (pin "P$8") (pinfunction "RTS_P$8") (pintype "input"))
      (node (ref "R36") (pin "1") (pinfunction "1_1") (pintype "passive"))
      (node (ref "U10") (pin "12") (pinfunction "6Y_12") (pintype "output"))
    )
    (net (code "26") (name "/GSM_RTS_H") (class "Default")
      (node (ref "IC1") (pin "16") (pinfunction "RB4_16") (pintype "bidirectional"))
      (node (ref "U10") (pin "13") (pinfunction "6A_13") (pintype "input"))
    )
    (net (code "27") (name "/GSM_RXD") (class "Default")
      (node (ref "IC2") (pin "P$10") (pinfunction "RXD_P$10") (pintype "input"))
      (node (ref "R37") (pin "1") (pinfunction "1_1") (pintype "passive"))
      (node (ref "U10") (pin "6") (pinfunction "3Y_6") (pintype "output"))
    )
    (net (code "28") (name "/GSM_RXD_H") (class "Default")
      (node (ref "IC1") (pin "18") (pinfunction "RB2_18") (pintype "bidirectional"))
      (node (ref "U10") (pin "5") (pinfunction "3A_5") (pintype "input"))
    )
    (net (code "29") (name "/GSM_STATUS") (class "Default")
      (node (ref "IC2") (pin "P$66") (pinfunction "STATUS_P$66") (pintype "bidirectional"))
      (node (ref "Q9") (pin "1") (pinfunction "G_1") (pintype "bidirectional"))
    )
    (net (code "30") (name "/GSM_STATUS_H") (class "Default")
      (node (ref "Q9") (pin "3") (pinfunction "D_3") (pintype "bidirectional"))
      (node (ref "R33") (pin "1") (pinfunction "1_1") (pintype "passive"))
    )
    (net (code "31") (name "/GSM_TXD") (class "Default")
      (node (ref "IC1") (pin "5") (pinfunction "RC3_5") (pintype "bidirectional"))
      (node (ref "IC2") (pin "P$9") (pinfunction "TXD_P$9") (pintype "output"))
    )
    (net (code "32") (name "/MISO") (class "Default")
      (node (ref "IC1") (pin "8") (pinfunction "RG8_8") (pintype "bidirectional"))
      (node (ref "J1") (pin "7") (pinfunction "7_7") (pintype "passive"))
      (node (ref "SLOT1") (pin "T7") (pinfunction "DAT0/D0_T7") (pintype "bidirectional"))
      (node (ref "U8") (pin "8") (pinfunction "SO_8") (pintype "output"))
    )
    (net (code "33") (name "/MOSI") (class "Default")
      (node (ref "IC1") (pin "6") (pinfunction "RG6_6") (pintype "bidirectional"))
      (node (ref "J1") (pin "6") (pinfunction "6_6") (pintype "passive"))
      (node (ref "SLOT1") (pin "T3") (pinfunction "CMD/MOSI_T3") (pintype "bidirectional"))
      (node (ref "U8") (pin "1") (pinfunction "SI_1") (pintype "input"))
    )
    (net (code "34") (name "/NETLIGHT") (class "Default")
      (node (ref "IC2") (pin "P$52") (pinfunction "NETLIGHT_P$52") (pintype "bidirectional"))
      (node (ref "Q10") (pin "1") (pinfunction "G_1") (pintype "bidirectional"))
    )
    (net (code "35") (name "/OSCI") (class "Default")
      (node (ref "C21") (pin "2") (pinfunction "2_2") (pintype "passive"))
      (node (ref "IC1") (pin "49") (pinfunction "RC12_49") (pintype "bidirectional"))
      (node (ref "Y1") (pin "1") (pinfunction "1_1") (pintype "passive"))
    )
    (net (code "36") (name "/OSCO") (class "Default")
      (node (ref "C20") (pin "2") (pinfunction "2_2") (pintype "passive"))
      (node (ref "IC1") (pin "50") (pinfunction "RC15_50") (pintype "bidirectional"))
      (node (ref "Y1") (pin "3") (pinfunction "2_3") (pintype "passive"))
    )
    (net (code "37") (name "/PGEC2") (class "Default")
      (node (ref "IC1") (pin "21") (pinfunction "RB6_21") (pintype "bidirectional"))
      (node (ref "J2") (pin "5") (pinfunction "5_5") (pintype "passive"))
    )
    (net (code "38") (name "/PGED2") (class "Default")
      (node (ref "IC1") (pin "22") (pinfunction "RB7_22") (pintype "bidirectional"))
      (node (ref "J2") (pin "4") (pinfunction "4_4") (pintype "passive"))
    )
    (net (code "39") (name "/PORT1_IO0") (class "Default")
      (node (ref "IC1") (pin "57") (pinfunction "RD11_57") (pintype "bidirectional"))
      (node (ref "X2") (pin "2") (pinfunction "S_2") (pintype "passive"))
    )
    (net (code "40") (name "/PORT1_IO1") (class "Default")
      (node (ref "IC1") (pin "58") (pinfunction "RD0_58") (pintype "bidirectional"))
      (node (ref "X2") (pin "3") (pinfunction "S_3") (pintype "passive"))
    )
    (net (code "41") (name "/PORT1_IO2") (class "Default")
      (node (ref "IC1") (pin "59") (pinfunction "RC13_59") (pintype "bidirectional"))
      (node (ref "X2") (pin "6") (pinfunction "S_6") (pintype "passive"))
    )
    (net (code "42") (name "/PORT1_IO3") (class "Default")
      (node (ref "IC1") (pin "60") (pinfunction "RC14_60") (pintype "bidirectional"))
      (node (ref "X2") (pin "7") (pinfunction "S_7") (pintype "passive"))
    )
    (net (code "43") (name "/PORT1_IOUT") (class "Default")
      (node (ref "Q2") (pin "5") (pinfunction "D_5") (pintype "passive"))
      (node (ref "Q2") (pin "6") (pinfunction "D_6") (pintype "passive"))
      (node (ref "Q2") (pin "7") (pinfunction "D_7") (pintype "passive"))
      (node (ref "Q2") (pin "8") (pinfunction "D_8") (pintype "passive"))
      (node (ref "Q2") (pin "9") (pinfunction "D_9") (pintype "passive"))
      (node (ref "R5") (pin "2") (pinfunction "2_2") (pintype "passive"))
      (node (ref "U2") (pin "4") (pinfunction "IN-_2_4") (pintype "input"))
      (node (ref "U2") (pin "5") (pinfunction "IN-_5") (pintype "input"))
    )
    (net (code "44") (name "/PORT1_ON") (class "Default")
      (node (ref "IC1") (pin "52") (pinfunction "RA14_52") (pintype "bidirectional"))
      (node (ref "Q4") (pin "1") (pinfunction "G_1") (pintype "bidirectional"))
      (node (ref "R12") (pin "2") (pinfunction "2_2") (pintype "passive"))
    )
    (net (code "45") (name "/PORT2_IO0") (class "Default")
      (node (ref "IC1") (pin "61") (pinfunction "RD1_61") (pintype "bidirectional"))
      (node (ref "X4") (pin "2") (pinfunction "S_2") (pintype "passive"))
    )
    (net (code "46") (name "/PORT2_IO1") (class "Default")
      (node (ref "IC1") (pin "62") (pinfunction "RD2_62") (pintype "bidirectional"))
      (node (ref "X4") (pin "3") (pinfunction "S_3") (pintype "passive"))
    )
    (net (code "47") (name "/PORT2_IO2") (class "Default")
      (node (ref "IC1") (pin "63") (pinfunction "RD3_63") (pintype "bidirectional"))
      (node (ref "X4") (pin "6") (pinfunction "S_6") (pintype "passive"))
    )
    (net (code "48") (name "/PORT2_IO3") (class "Default")
      (node (ref "X4") (pin "7") (pinfunction "S_7") (pintype "passive"))
    )
    (net (code "49") (name "/PORT2_IOUT") (class "Default")
      (node (ref "Q6") (pin "5") (pinfunction "D_5") (pintype "passive"))
      (node (ref "Q6") (pin "6") (pinfunction "D_6") (pintype "passive"))
      (node (ref "Q6") (pin "7") (pinfunction "D_7") (pintype "passive"))
      (node (ref "Q6") (pin "8") (pinfunction "D_8") (pintype "passive"))
      (node (ref "Q6") (pin "9") (pinfunction "D_9") (pintype "passive"))
      (node (ref "R16") (pin "2") (pinfunction "2_2") (pintype "passive"))
      (node (ref "U4") (pin "4") (pinfunction "IN-_2_4") (pintype "input"))
      (node (ref "U4") (pin "5") (pinfunction "IN-_5") (pintype "input"))
    )
    (net (code "50") (name "/PORT2_ON") (class "Default")
      (node (ref "IC1") (pin "53") (pinfunction "RA15_53") (pintype "bidirectional"))
      (node (ref "Q7") (pin "1") (pinfunction "G_1") (pintype "bidirectional"))
      (node (ref "R21") (pin "2") (pinfunction "2_2") (pintype "passive"))
    )
    (net (code "51") (name "/PWRKEY") (class "Default")
      (node (ref "IC2") (pin "P$1") (pinfunction "PWRKEY_P$1") (pintype "power_in"))
      (node (ref "U10") (pin "8") (pinfunction "4Y_8") (pintype "output"))
    )
    (net (code "52") (name "/PWRKEY_H") (class "Default")
      (node (ref "IC1") (pin "10") (pinfunction "RG9_10") (pintype "bidirectional"))
      (node (ref "U10") (pin "9") (pinfunction "4A_9") (pintype "input"))
    )
    (net (code "53") (name "/RF_CE") (class "Default")
      (node (ref "IC1") (pin "79") (pinfunction "RE3_79") (pintype "bidirectional"))
      (node (ref "J1") (pin "3") (pinfunction "3_3") (pintype "passive"))
    )
    (net (code "54") (name "/RF_IRQ") (class "Default")
      (node (ref "IC1") (pin "77") (pinfunction "RE1_77") (pintype "bidirectional"))
      (node (ref "J1") (pin "8") (pinfunction "8_8") (pintype "passive"))
    )
    (net (code "55") (name "/RPI38") (class "Default")
      (node (ref "IC1") (pin "4") (pinfunction "RC1_4") (pintype "bidirectional"))
    )
    (net (code "56") (name "/RT") (class "Default")
      (node (ref "R14") (pin "2") (pinfunction "2_2") (pintype "passive"))
      (node (ref "U3") (pin "2") (pinfunction "RT_2") (pintype "output"))
    )
    (net (code "57") (name "/SCL1") (class "Default")
      (node (ref "IC1") (pin "56") (pinfunction "RD10_56") (pintype "bidirectional"))
      (node (ref "R22") (pin "1") (pinfunction "1_1") (pintype "passive"))
      (node (ref "U11") (pin "4") (pinfunction "SCL_4") (pintype "input"))
    )
    (net (code "58") (name "/SCLK") (class "Default")
      (node (ref "IC1") (pin "7") (pinfunction "RG7_7") (pintype "bidirectional"))
      (node (ref "J1") (pin "5") (pinfunction "5_5") (pintype "passive"))
      (node (ref "SLOT1") (pin "T5") (pinfunction "CLK/SCLK_T5") (pintype "bidirectional"))
      (node (ref "U8") (pin "2") (pinfunction "SCK_2") (pintype "input"))
    )
    (net (code "59") (name "/SDA1") (class "Default")
      (node (ref "IC1") (pin "55") (pinfunction "RD9_55") (pintype "bidirectional"))
      (node (ref "R23") (pin "1") (pinfunction "1_1") (pintype "passive"))
      (node (ref "U11") (pin "6") (pinfunction "SDA_6") (pintype "bidirectional"))
    )
    (net (code "60") (name "/SD_VDD") (class "Default")
      (node (ref "C19") (pin "1") (pinfunction "1_1") (pintype "passive"))
      (node (ref "Q8") (pin "3") (pinfunction "D_3") (pintype "passive"))
      (node (ref "R25") (pin "2") (pinfunction "2_2") (pintype "passive"))
      (node (ref "SLOT1") (pin "T4") (pinfunction "VDD_T4") (pintype "bidirectional"))
    )
    (net (code "61") (name "/SENSE_5V") (class "Default")
      (node (ref "IC1") (pin "17") (pinfunction "RB3_17") (pintype "bidirectional"))
      (node (ref "R4") (pin "1") (pinfunction "1_1") (pintype "passive"))
      (node (ref "R8") (pin "2") (pinfunction "2_2") (pintype "passive"))
    )
    (net (code "62") (name "/SIM_CLK") (class "Default")
      (node (ref "IC2") (pin "P$32") (pinfunction "SIM_CLK_P$32") (pintype "bidirectional"))
      (node (ref "R27") (pin "2") (pinfunction "2_2") (pintype "passive"))
      (node (ref "U7") (pin "5") (pinfunction "5_5") (pintype "bidirectional"))
    )
    (net (code "63") (name "/SIM_DATA") (class "Default")
      (node (ref "IC2") (pin "P$31") (pinfunction "SIM_DATA_P$31") (pintype "bidirectional"))
      (node (ref "R28") (pin "2") (pinfunction "2_2") (pintype "passive"))
      (node (ref "U7") (pin "4") (pinfunction "4_4") (pintype "bidirectional"))
    )
    (net (code "64") (name "/SIM_RST") (class "Default")
      (node (ref "IC2") (pin "P$33") (pinfunction "SIM_RST_P$33") (pintype "bidirectional"))
      (node (ref "R26") (pin "2") (pinfunction "2_2") (pintype "passive"))
      (node (ref "U7") (pin "6") (pinfunction "6_6") (pintype "bidirectional"))
    )
    (net (code "65") (name "/SIM_VDD") (class "Default")
      (node (ref "C23") (pin "1") (pinfunction "1_1") (pintype "passive"))
      (node (ref "IC2") (pin "P$30") (pinfunction "SIM_VDD_P$30") (pintype "power_in"))
      (node (ref "SLOT1") (pin "S1") (pinfunction "SIM_VCC_S1") (pintype "bidirectional"))
      (node (ref "U7") (pin "1") (pinfunction "1_1") (pintype "bidirectional"))
    )
    (net (code "66") (name "/U2_RTS") (class "Default")
      (node (ref "IC1") (pin "64") (pinfunction "RD12_64") (pintype "bidirectional"))
      (node (ref "X5") (pin "4") (pinfunction "S_4") (pintype "passive"))
    )
    (net (code "67") (name "/U2_RXD") (class "Default")
      (node (ref "IC1") (pin "67") (pinfunction "RD5_67") (pintype "bidirectional"))
      (node (ref "X5") (pin "2") (pinfunction "S_2") (pintype "passive"))
    )
    (net (code "68") (name "/U2_TXD") (class "Default")
      (node (ref "IC1") (pin "66") (pinfunction "RD4_66") (pintype "bidirectional"))
      (node (ref "X5") (pin "3") (pinfunction "S_3") (pintype "passive"))
    )
    (net (code "69") (name "/UD_N") (class "Default")
      (node (ref "IC1") (pin "46") (pinfunction "RG3_46") (pintype "bidirectional"))
      (node (ref "USB1") (pin "2") (pinfunction "D-_2") (pintype "bidirectional"))
    )
    (net (code "70") (name "/UD_P") (class "Default")
      (node (ref "IC1") (pin "47") (pinfunction "RG2_47") (pintype "bidirectional"))
      (node (ref "USB1") (pin "3") (pinfunction "D+_3") (pintype "bidirectional"))
    )
    (net (code "71") (name "/USB_VBUS") (class "Default")
      (node (ref "C25") (pin "2") (pinfunction "2_2") (pintype "passive"))
      (node (ref "C28") (pin "2") (pinfunction "2_2") (pintype "passive"))
      (node (ref "IC1") (pin "44") (pinfunction "VBUS_44") (pintype "passive"))
      (node (ref "USB1") (pin "1") (pinfunction "VBUS_1") (pintype "power_in"))
    )
    (net (code "72") (name "/VRTC") (class "Default")
      (node (ref "D2") (pin "C") (pinfunction "C_C") (pintype "passive"))
      (node (ref "IC2") (pin "P$26") (pinfunction "VRTC_P$26") (pintype "power_in"))
    )
    (net (code "73") (name "/~{FLASH_CS}") (class "Default")
      (node (ref "IC1") (pin "80") (pinfunction "RE4_80") (pintype "bidirectional"))
      (node (ref "R31") (pin "2") (pinfunction "2_2") (pintype "passive"))
      (node (ref "U8") (pin "4") (pinfunction "~{CS}_4") (pintype "input"))
    )
    (net (code "74") (name "/~{FLASH_RESET}") (class "Default")
      (node (ref "IC1") (pin "1") (pinfunction "RE5_1") (pintype "bidirectional"))
      (node (ref "R30") (pin "2") (pinfunction "2_2") (pintype "passive"))
      (node (ref "U8") (pin "3") (pinfunction "~{RESET}_3") (pintype "input"))
    )
    (net (code "75") (name "/~{MCLR}") (class "Default")
      (node (ref "IC1") (pin "9") (pinfunction "~{MCLR}_9") (pintype "bidirectional"))
      (node (ref "J2") (pin "1") (pinfunction "1_1") (pintype "passive"))
      (node (ref "R29") (pin "2") (pinfunction "2_2") (pintype "passive"))
    )
    (net (code "76") (name "/~{RF_CS}") (class "Default")
      (node (ref "IC1") (pin "78") (pinfunction "RE2_78") (pintype "bidirectional"))
      (node (ref "J1") (pin "4") (pinfunction "4_4") (pintype "passive"))
    )
    (net (code "77") (name "/~{SD_CS}") (class "Default")
      (node (ref "IC1") (pin "2") (pinfunction "RE6_2") (pintype "bidirectional"))
      (node (ref "R25") (pin "1") (pinfunction "1_1") (pintype "passive"))
      (node (ref "SLOT1") (pin "T2") (pinfunction "CD/DAT3/~{CS}_T2") (pintype "bidirectional"))
    )
    (net (code "78") (name "/~{SD_ON}") (class "Default")
      (node (ref "IC1") (pin "3") (pinfunction "RE7_3") (pintype "bidirectional"))
      (node (ref "Q8") (pin "1") (pinfunction "G_1") (pintype "passive"))
      (node (ref "R24") (pin "1") (pinfunction "1_1") (pintype "passive"))
    )
    (net (code "79") (name "2.8V") (class "Default")
      (node (ref "IC2") (pin "P$15") (pinfunction "VDD_EXT_P$15") (pintype "bidirectional"))
      (node (ref "R35") (pin "2") (pinfunction "2_2") (pintype "passive"))
      (node (ref "R36") (pin "2") (pinfunction "2_2") (pintype "passive"))
      (node (ref "R37") (pin "2") (pinfunction "2_2") (pintype "passive"))
      (node (ref "R38") (pin "2") (pinfunction "2_2") (pintype "passive"))
    )
    (net (code "80") (name "3.8V") (class "Default")
      (node (ref "C16") (pin "+") (pinfunction "+_+") (pintype "passive"))
      (node (ref "C17") (pin "+") (pinfunction "+_+") (pintype "passive"))
      (node (ref "C38") (pin "2") (pinfunction "2_2") (pintype "passive"))
      (node (ref "C39") (pin "2") (pinfunction "2_2") (pintype "passive"))
      (node (ref "C40") (pin "2") (pinfunction "2_2") (pintype "passive"))
      (node (ref "C41") (pin "2") (pinfunction "2_2") (pintype "passive"))
      (node (ref "C42") (pin "2") (pinfunction "2_2") (pintype "passive"))
      (node (ref "C43") (pin "2") (pinfunction "2_2") (pintype "passive"))
      (node (ref "IC2") (pin "P$55") (pinfunction "VBAT1_P$55") (pintype "power_in"))
      (node (ref "IC2") (pin "P$56") (pinfunction "VBAT2_P$56") (pintype "power_in"))
      (node (ref "IC2") (pin "P$57") (pinfunction "VBAT3_P$57") (pintype "power_in"))
      (node (ref "LED2") (pin "A") (pinfunction "A_A") (pintype "passive"))
      (node (ref "LED3") (pin "A") (pinfunction "A_A") (pintype "passive"))
      (node (ref "LED4") (pin "A") (pinfunction "A_A") (pintype "passive"))
      (node (ref "LED5") (pin "A") (pinfunction "A_A") (pintype "passive"))
      (node (ref "R18") (pin "2") (pinfunction "2_2") (pintype "passive"))
      (node (ref "TP8") (pin "TP") (pinfunction "TP_TP") (pintype "input"))
      (node (ref "U6") (pin "4") (pinfunction "OUT_4") (pintype "output"))
    )
    (net (code "81") (name "GND") (class "Default")
      (node (ref "ANT1") (pin "P$1") (pinfunction "GND_P$1") (pintype "bidirectional"))
      (node (ref "ANT1") (pin "P$2") (pinfunction "GND_P$2") (pintype "bidirectional"))
      (node (ref "BAT1") (pin "N") (pinfunction "-_N") (pintype "passive"))
      (node (ref "C1") (pin "2") (pinfunction "2_2") (pintype "passive"))
      (node (ref "C10") (pin "2") (pinfunction "2_2") (pintype "passive"))
      (node (ref "C11") (pin "2") (pinfunction "2_2") (pintype "passive"))
      (node (ref "C12") (pin "2") (pinfunction "2_2") (pintype "passive"))
      (node (ref "C13") (pin "-") (pinfunction "-_-") (pintype "passive"))
      (node (ref "C14") (pin "-") (pinfunction "-_-") (pintype "passive"))
      (node (ref "C15") (pin "-") (pinfunction "-_-") (pintype "passive"))
      (node (ref "C16") (pin "-") (pinfunction "-_-") (pintype "passive"))
      (node (ref "C17") (pin "-") (pinfunction "-_-") (pintype "passive"))
      (node (ref "C18") (pin "1") (pinfunction "1_1") (pintype "passive"))
      (node (ref "C19") (pin "2") (pinfunction "2_2") (pintype "passive"))
      (node (ref "C2") (pin "2") (pinfunction "2_2") (pintype "passive"))
      (node (ref "C20") (pin "1") (pinfunction "1_1") (pintype "passive"))
      (node (ref "C21") (pin "1") (pinfunction "1_1") (pintype "passive"))
      (node (ref "C22") (pin "2") (pinfunction "2_2") (pintype "passive"))
      (node (ref "C23") (pin "2") (pinfunction "2_2") (pintype "passive"))
      (node (ref "C24") (pin "2") (pinfunction "2_2") (pintype "passive"))
      (node (ref "C25") (pin "1") (pinfunction "1_1") (pintype "passive"))
      (node (ref "C26") (pin "1") (pinfunction "1_1") (pintype "passive"))
      (node (ref "C27") (pin "1") (pinfunction "1_1") (pintype "passive"))
      (node (ref "C28") (pin "1") (pinfunction "1_1") (pintype "passive"))
      (node (ref "C29") (pin "2") (pinfunction "2_2") (pintype "passive"))
      (node (ref "C30") (pin "2") (pinfunction "2_2") (pintype "passive"))
      (node (ref "C31") (pin "2") (pinfunction "2_2") (pintype "passive"))
      (node (ref "C32") (pin "2") (pinfunction "2_2") (pintype "passive"))
      (node (ref "C33") (pin "2") (pinfunction "2_2") (pintype "passive"))
      (node (ref "C34") (pin "2") (pinfunction "2_2") (pintype "passive"))
      (node (ref "C35") (pin "2") (pinfunction "2_2") (pintype "passive"))
      (node (ref "C36") (pin "2") (pinfunction "2_2") (pintype "passive"))
      (node (ref "C37") (pin "2") (pinfunction "2_2") (pintype "passive"))
      (node (ref "C38") (pin "1") (pinfunction "1_1") (pintype "passive"))
      (node (ref "C39") (pin "1") (pinfunction "1_1") (pintype "passive"))
      (node (ref "C40") (pin "1") (pinfunction "1_1") (pintype "passive"))
      (node (ref "C41") (pin "1") (pinfunction "1_1") (pintype "passive"))
      (node (ref "C42") (pin "1") (pinfunction "1_1") (pintype "passive"))
      (node (ref "C43") (pin "1") (pinfunction "1_1") (pintype "passive"))
      (node (ref "C7") (pin "2") (pinfunction "2_2") (pintype "passive"))
      (node (ref "C8") (pin "2") (pinfunction "2_2") (pintype "passive"))
      (node (ref "C9") (pin "2") (pinfunction "2_2") (pintype "passive"))
      (node (ref "D1") (pin "1") (pinfunction "A1_1") (pintype "passive"))
      (node (ref "D1") (pin "3") (pinfunction "A2_3") (pintype "passive"))
      (node (ref "IC1") (pin "11") (pinfunction "VSS_11") (pintype "power_in"))
      (node (ref "IC1") (pin "26") (pinfunction "AVSS_26") (pintype "power_in"))
      (node (ref "IC1") (pin "31") (pinfunction "VSS_31") (pintype "power_in"))
      (node (ref "IC1") (pin "51") (pinfunction "VSS_51") (pintype "power_in"))
      (node (ref "IC2") (pin "P$17") (pinfunction "GND1_P$17") (pintype "power_in"))
      (node (ref "IC2") (pin "P$18") (pinfunction "GND2_P$18") (pintype "power_in"))
      (node (ref "IC2") (pin "P$29") (pinfunction "GND3_P$29") (pintype "power_in"))
      (node (ref "IC2") (pin "P$39") (pinfunction "GND4_P$39") (pintype "power_in"))
      (node (ref "IC2") (pin "P$45") (pinfunction "GND5_P$45") (pintype "power_in"))
      (node (ref "IC2") (pin "P$46") (pinfunction "GND6_P$46") (pintype "power_in"))
      (node (ref "IC2") (pin "P$53") (pinfunction "GND7_P$53") (pintype "power_in"))
      (node (ref "IC2") (pin "P$54") (pinfunction "GND8_P$54") (pintype "power_in"))
      (node (ref "IC2") (pin "P$58") (pinfunction "GND9_P$58") (pintype "power_in"))
      (node (ref "IC2") (pin "P$59") (pinfunction "GND10_P$59") (pintype "power_in"))
      (node (ref "IC2") (pin "P$61") (pinfunction "GND11_P$61") (pintype "power_in"))
      (node (ref "IC2") (pin "P$62") (pinfunction "GND12_P$62") (pintype "power_in"))
      (node (ref "IC2") (pin "P$63") (pinfunction "GND13_P$63") (pintype "power_in"))
      (node (ref "IC2") (pin "P$64") (pinfunction "GND14_P$64") (pintype "power_in"))
      (node (ref "IC2") (pin "P$65") (pinfunction "GND15_P$65") (pintype "power_in"))
      (node (ref "J1") (pin "1") (pinfunction "1_1") (pintype "passive"))
      (node (ref "J2") (pin "3") (pinfunction "3_3") (pintype "passive"))
      (node (ref "JMP1") (pin "3") (pinfunction "3_3") (pintype "passive"))
      (node (ref "JMP2") (pin "3") (pinfunction "3_3") (pintype "passive"))
      (node (ref "Q10") (pin "2") (pinfunction "S_2") (pintype "bidirectional"))
      (node (ref "Q4") (pin "2") (pinfunction "S_2") (pintype "bidirectional"))
      (node (ref "Q7") (pin "2") (pinfunction "S_2") (pintype "bidirectional"))
      (node (ref "Q9") (pin "2") (pinfunction "S_2") (pintype "bidirectional"))
      (node (ref "R12") (pin "1") (pinfunction "1_1") (pintype "passive"))
      (node (ref "R15") (pin "1") (pinfunction "1_1") (pintype "passive"))
      (node (ref "R19") (pin "1") (pinfunction "1_1") (pintype "passive"))
      (node (ref "R20") (pin "1") (pinfunction "1_1") (pintype "passive"))
      (node (ref "R21") (pin "1") (pinfunction "1_1") (pintype "passive"))
      (node (ref "R29") (pin "1") (pinfunction "1_1") (pintype "passive"))
      (node (ref "R3") (pin "1") (pinfunction "1_1") (pintype "passive"))
      (node (ref "R34") (pin "1") (pinfunction "1_1") (pintype "passive"))
      (node (ref "R7") (pin "1") (pinfunction "1_1") (pintype "passive"))
      (node (ref "R8") (pin "1") (pinfunction "1_1") (pintype "passive"))
      (node (ref "SLOT1") (pin "S4") (pinfunction "SIM_GND_S4") (pintype "bidirectional"))
      (node (ref "SLOT1") (pin "T6") (pinfunction "VSS_T6") (pintype "bidirectional"))
      (node (ref "TP6") (pin "TP") (pinfunction "TP_TP") (pintype "input"))
      (node (ref "TP7") (pin "TP") (pinfunction "TP_TP") (pintype "input"))
      (node (ref "U1") (pin "9") (pinfunction "GND_9") (pintype "passive"))
      (node (ref "U10") (pin "7") (pinfunction "GND_7") (pintype "passive"))
      (node (ref "U11") (pin "10") (pinfunction "GND_10_10") (pintype "passive"))
      (node (ref "U11") (pin "12") (pinfunction "GND_12_12") (pintype "passive"))
      (node (ref "U11") (pin "15") (pinfunction "GND_15_15") (pintype "passive"))
      (node (ref "U11") (pin "5") (pinfunction "GND_5_5") (pintype "passive"))
      (node (ref "U11") (pin "7") (pinfunction "SA0_7") (pintype "input"))
      (node (ref "U2") (pin "9") (pinfunction "GND_9") (pintype "passive"))
      (node (ref "U3") (pin "4") (pinfunction "GND_4") (pintype "passive"))
      (node (ref "U4") (pin "9") (pinfunction "GND_9") (pintype "passive"))
      (node (ref "U5") (pin "1") (pinfunction "ADJ_1") (pintype "input"))
      (node (ref "U6") (pin "3") (pinfunction "GND_3") (pintype "passive"))
      (node (ref "U6") (pin "TAB") (pinfunction "GND_TAB") (pintype "passive"))
      (node (ref "U7") (pin "2") (pinfunction "2_2") (pintype "bidirectional"))
      (node (ref "U8") (pin "7") (pinfunction "GND_7") (pintype "passive"))
      (node (ref "U9") (pin "3") (pinfunction "GND_3") (pintype "passive"))
      (node (ref "USB1") (pin "5") (pinfunction "GND_5") (pintype "power_in"))
      (node (ref "X1") (pin "3") (pinfunction "S_3") (pintype "passive"))
      (node (ref "X1") (pin "4") (pinfunction "S_4") (pintype "passive"))
      (node (ref "X2") (pin "4") (pinfunction "S_4") (pintype "passive"))
      (node (ref "X2") (pin "8") (pinfunction "S_8") (pintype "passive"))
      (node (ref "X3") (pin "2") (pinfunction "S_2") (pintype "passive"))
      (node (ref "X4") (pin "4") (pinfunction "S_4") (pintype "passive"))
      (node (ref "X4") (pin "8") (pinfunction "S_8") (pintype "passive"))
      (node (ref "X5") (pin "5") (pinfunction "S_5") (pintype "passive"))
      (node (ref "Y1") (pin "2") (pinfunction "4_2") (pintype "passive"))
      (node (ref "Y1") (pin "4") (pinfunction "4_4") (pintype "passive"))
    )
    (net (code "82") (name "Net-(ANT1-SIGNAL)") (class "Default")
      (node (ref "ANT1") (pin "P$3") (pinfunction "SIGNAL_P$3") (pintype "bidirectional"))
      (node (ref "IC2") (pin "P$60") (pinfunction "RF_ANT_P$60") (pintype "bidirectional"))
    )
    (net (code "83") (name "Net-(BAT1-+)") (class "Default")
      (node (ref "BAT1") (pin "P") (pinfunction "+_P") (pintype "passive"))
      (node (ref "D2") (pin "A") (pinfunction "A_A") (pintype "passive"))
    )
    (net (code "84") (name "Net-(C3-Pad1)") (class "Default")
      (node (ref "C3") (pin "1") (pinfunction "1_1") (pintype "passive"))
      (node (ref "C4") (pin "2") (pinfunction "2_2") (pintype "passive"))
      (node (ref "R6") (pin "2") (pinfunction "2_2") (pintype "passive"))
    )
    (net (code "85") (name "Net-(CONN1-P$2)") (class "Default")
      (node (ref "CONN1") (pin "2") (pinfunction "P$2_2") (pintype "power_in"))
      (node (ref "R2") (pin "1") (pinfunction "1_1") (pintype "passive"))
      (node (ref "U1") (pin "2") (pinfunction "IN+_2") (pintype "input"))
      (node (ref "U1") (pin "3") (pinfunction "IN+_2_3") (pintype "input"))
    )
    (net (code "86") (name "Net-(D1-C)") (class "Default")
      (node (ref "D1") (pin "4") (pinfunction "C_4") (pintype "passive"))
      (node (ref "L1") (pin "1") (pinfunction "1_1") (pintype "passive"))
      (node (ref "Q3") (pin "5") (pinfunction "D_5") (pintype "passive"))
      (node (ref "Q3") (pin "6") (pinfunction "D_6") (pintype "passive"))
      (node (ref "Q3") (pin "7") (pinfunction "D_7") (pintype "passive"))
      (node (ref "Q3") (pin "8") (pinfunction "D_8") (pintype "passive"))
      (node (ref "Q3") (pin "D1") (pinfunction "D_D1") (pintype "passive"))
      (node (ref "Q3") (pin "D2") (pinfunction "D_D2") (pintype "passive"))
      (node (ref "Q3") (pin "D3") (pinfunction "D_D3") (pintype "passive"))
      (node (ref "R6") (pin "1") (pinfunction "1_1") (pintype "passive"))
    )
    (net (code "87") (name "Net-(IC1-VDDCORE)") (class "Default")
      (node (ref "C18") (pin "2") (pinfunction "2_2") (pintype "passive"))
      (node (ref "IC1") (pin "70") (pinfunction "VDDCORE_70") (pintype "power_in"))
    )
    (net (code "88") (name "Net-(LED1-PadC)") (class "Default")
      (node (ref "LED1") (pin "C") (pinfunction "C_C") (pintype "passive"))
      (node (ref "R7") (pin "2") (pinfunction "2_2") (pintype "passive"))
    )
    (net (code "89") (name "Net-(LED2-PadC)") (class "Default")
      (node (ref "LED2") (pin "C") (pinfunction "C_C") (pintype "passive"))
      (node (ref "R19") (pin "2") (pinfunction "2_2") (pintype "passive"))
    )
    (net (code "90") (name "Net-(LED3-PadC)") (class "Default")
      (node (ref "LED3") (pin "C") (pinfunction "C_C") (pintype "passive"))
      (node (ref "R34") (pin "2") (pinfunction "2_2") (pintype "passive"))
    )
    (net (code "91") (name "Net-(LED4-PadC)") (class "Default")
      (node (ref "LED4") (pin "C") (pinfunction "C_C") (pintype "passive"))
      (node (ref "R32") (pin "2") (pinfunction "2_2") (pintype "passive"))
    )
    (net (code "92") (name "Net-(LED5-PadC)") (class "Default")
      (node (ref "LED5") (pin "C") (pinfunction "C_C") (pintype "passive"))
      (node (ref "R33") (pin "2") (pinfunction "2_2") (pintype "passive"))
    )
    (net (code "93") (name "Net-(Q1-G)") (class "Default")
      (node (ref "Q1") (pin "4") (pinfunction "G_4") (pintype "passive"))
      (node (ref "Q2") (pin "4") (pinfunction "G_4") (pintype "passive"))
      (node (ref "Q4") (pin "3") (pinfunction "D_3") (pintype "bidirectional"))
      (node (ref "R10") (pin "1") (pinfunction "1_1") (pintype "passive"))
    )
    (net (code "94") (name "Net-(Q1-S-Pad1)") (class "Default")
      (node (ref "Q1") (pin "1") (pinfunction "S_1") (pintype "passive"))
      (node (ref "Q1") (pin "2") (pinfunction "S_2") (pintype "passive"))
      (node (ref "Q1") (pin "3") (pinfunction "S_3") (pintype "passive"))
      (node (ref "Q1") (pin "3B") (pinfunction "S_3B") (pintype "passive"))
      (node (ref "Q2") (pin "1") (pinfunction "S_1") (pintype "passive"))
      (node (ref "Q2") (pin "2") (pinfunction "S_2") (pintype "passive"))
      (node (ref "Q2") (pin "3") (pinfunction "S_3") (pintype "passive"))
      (node (ref "Q2") (pin "3B") (pinfunction "S_3B") (pintype "passive"))
      (node (ref "R10") (pin "2") (pinfunction "2_2") (pintype "passive"))
    )
    (net (code "95") (name "Net-(Q3-G)") (class "Default")
      (node (ref "Q3") (pin "4") (pinfunction "G_4") (pintype "passive"))
      (node (ref "TP4") (pin "TP") (pinfunction "TP_TP") (pintype "input"))
      (node (ref "U3") (pin "6") (pinfunction "PGATE_6") (pintype "output"))
    )
    (net (code "96") (name "Net-(Q5-G)") (class "Default")
      (node (ref "Q5") (pin "4") (pinfunction "G_4") (pintype "passive"))
      (node (ref "Q6") (pin "4") (pinfunction "G_4") (pintype "passive"))
      (node (ref "Q7") (pin "3") (pinfunction "D_3") (pintype "bidirectional"))
      (node (ref "R17") (pin "1") (pinfunction "1_1") (pintype "passive"))
    )
    (net (code "97") (name "Net-(Q5-S-Pad1)") (class "Default")
      (node (ref "Q5") (pin "1") (pinfunction "S_1") (pintype "passive"))
      (node (ref "Q5") (pin "2") (pinfunction "S_2") (pintype "passive"))
      (node (ref "Q5") (pin "3") (pinfunction "S_3") (pintype "passive"))
      (node (ref "Q5") (pin "3B") (pinfunction "S_3B") (pintype "passive"))
      (node (ref "Q6") (pin "1") (pinfunction "S_1") (pintype "passive"))
      (node (ref "Q6") (pin "2") (pinfunction "S_2") (pintype "passive"))
      (node (ref "Q6") (pin "3") (pinfunction "S_3") (pintype "passive"))
      (node (ref "Q6") (pin "3B") (pinfunction "S_3B") (pintype "passive"))
      (node (ref "R17") (pin "2") (pinfunction "2_2") (pintype "passive"))
    )
    (net (code "98") (name "Net-(Q10-D)") (class "Default")
      (node (ref "Q10") (pin "3") (pinfunction "D_3") (pintype "bidirectional"))
      (node (ref "R32") (pin "1") (pinfunction "1_1") (pintype "passive"))
    )
    (net (code "99") (name "Net-(SLOT1-SIM_CLK)") (class "Default")
      (node (ref "R27") (pin "1") (pinfunction "1_1") (pintype "passive"))
      (node (ref "SLOT1") (pin "S3") (pinfunction "SIM_CLK_S3") (pintype "bidirectional"))
    )
    (net (code "100") (name "Net-(SLOT1-SIM_I{slash}O)") (class "Default")
      (node (ref "C22") (pin "1") (pinfunction "1_1") (pintype "passive"))
      (node (ref "R28") (pin "1") (pinfunction "1_1") (pintype "passive"))
      (node (ref "SLOT1") (pin "S6") (pinfunction "SIM_I/O_S6") (pintype "bidirectional"))
    )
    (net (code "101") (name "Net-(SLOT1-~{SIM_RESET})") (class "Default")
      (node (ref "R26") (pin "1") (pinfunction "1_1") (pintype "passive"))
      (node (ref "SLOT1") (pin "S2") (pinfunction "~{SIM_RESET}_S2") (pintype "bidirectional"))
    )
    (net (code "102") (name "Net-(U2-REF)") (class "Default")
      (node (ref "JMP1") (pin "2") (pinfunction "2_2") (pintype "passive"))
      (node (ref "U2") (pin "8") (pinfunction "REF_8") (pintype "input"))
    )
    (net (code "103") (name "Net-(U3-ADJ)") (class "Default")
      (node (ref "C6") (pin "2") (pinfunction "2_2") (pintype "passive"))
      (node (ref "R13") (pin "2") (pinfunction "2_2") (pintype "passive"))
      (node (ref "U3") (pin "1") (pinfunction "ADJ_1") (pintype "output"))
    )
    (net (code "104") (name "Net-(U3-FB)") (class "Default")
      (node (ref "C3") (pin "2") (pinfunction "2_2") (pintype "passive"))
      (node (ref "R11") (pin "1") (pinfunction "1_1") (pintype "passive"))
      (node (ref "R15") (pin "2") (pinfunction "2_2") (pintype "passive"))
      (node (ref "TP5") (pin "TP") (pinfunction "TP_TP") (pintype "input"))
      (node (ref "U3") (pin "3") (pinfunction "FB_3") (pintype "output"))
    )
    (net (code "105") (name "Net-(U3-ISEN)") (class "Default")
      (node (ref "Q3") (pin "1") (pinfunction "S_1") (pintype "passive"))
      (node (ref "Q3") (pin "2") (pinfunction "S_2") (pintype "passive"))
      (node (ref "Q3") (pin "3") (pinfunction "S_3") (pintype "passive"))
      (node (ref "R9") (pin "2") (pinfunction "2_2") (pintype "passive"))
      (node (ref "TP2") (pin "TP") (pinfunction "TP_TP") (pintype "input"))
      (node (ref "U3") (pin "5") (pinfunction "ISEN_5") (pintype "output"))
    )
    (net (code "106") (name "Net-(U3-VCC)") (class "Default")
      (node (ref "C5") (pin "2") (pinfunction "2_2") (pintype "passive"))
      (node (ref "U3") (pin "7") (pinfunction "VCC_7") (pintype "output"))
    )
    (net (code "107") (name "Net-(U4-REF)") (class "Default")
      (node (ref "JMP2") (pin "2") (pinfunction "2_2") (pintype "passive"))
      (node (ref "U4") (pin "8") (pinfunction "REF_8") (pintype "input"))
    )
    (net (code "108") (name "Net-(U6-ADJ)") (class "Default")
      (node (ref "R18") (pin "1") (pinfunction "1_1") (pintype "passive"))
      (node (ref "R20") (pin "2") (pinfunction "2_2") (pintype "passive"))
      (node (ref "U6") (pin "5") (pinfunction "ADJ_5") (pintype "input"))
    )
    (net (code "109") (name "Net-(U11-BYP)") (class "Default")
      (node (ref "C35") (pin "1") (pinfunction "1_1") (pintype "passive"))
      (node (ref "U11") (pin "2") (pinfunction "BYP_2") (pintype "input"))
    )
    (net (code "110") (name "Net-(X2A-S)") (class "Default")
      (node (ref "Q1") (pin "5") (pinfunction "D_5") (pintype "passive"))
      (node (ref "Q1") (pin "6") (pinfunction "D_6") (pintype "passive"))
      (node (ref "Q1") (pin "7") (pinfunction "D_7") (pintype "passive"))
      (node (ref "Q1") (pin "8") (pinfunction "D_8") (pintype "passive"))
      (node (ref "Q1") (pin "9") (pinfunction "D_9") (pintype "passive"))
      (node (ref "X2") (pin "1") (pinfunction "S_1") (pintype "passive"))
      (node (ref "X2") (pin "5") (pinfunction "S_5") (pintype "passive"))
    )
    (net (code "111") (name "Net-(X4A-S)") (class "Default")
      (node (ref "Q5") (pin "5") (pinfunction "D_5") (pintype "passive"))
      (node (ref "Q5") (pin "6") (pinfunction "D_6") (pintype "passive"))
      (node (ref "Q5") (pin "7") (pinfunction "D_7") (pintype "passive"))
      (node (ref "Q5") (pin "8") (pinfunction "D_8") (pintype "passive"))
      (node (ref "Q5") (pin "9") (pinfunction "D_9") (pintype "passive"))
      (node (ref "X4") (pin "1") (pinfunction "S_1") (pintype "passive"))
      (node (ref "X4") (pin "5") (pinfunction "S_5") (pintype "passive"))
    )
    (net (code "112") (name "V+") (class "Default")
      (node (ref "C15") (pin "+") (pinfunction "+_+") (pintype "passive"))
      (node (ref "CONN1") (pin "1") (pinfunction "P$1_1") (pintype "power_in"))
      (node (ref "U5") (pin "3") (pinfunction "IN_3") (pintype "input"))
      (node (ref "X1") (pin "1") (pinfunction "S_1") (pintype "passive"))
      (node (ref "X1") (pin "2") (pinfunction "S_2") (pintype "passive"))
    )
    (net (code "113") (name "unconnected-(IC1-RB8-Pad27)") (class "Default")
      (node (ref "IC1") (pin "27") (pinfunction "RB8_27") (pintype "bidirectional"))
    )
    (net (code "114") (name "unconnected-(IC1-RB9-Pad28)") (class "Default")
      (node (ref "IC1") (pin "28") (pinfunction "RB9_28") (pintype "bidirectional"))
    )
    (net (code "115") (name "unconnected-(IC1-RB10-Pad29)") (class "Default")
      (node (ref "IC1") (pin "29") (pinfunction "RB10_29") (pintype "bidirectional"))
    )
    (net (code "116") (name "unconnected-(IC1-RB11-Pad30)") (class "Default")
      (node (ref "IC1") (pin "30") (pinfunction "RB11_30") (pintype "bidirectional"))
    )
    (net (code "117") (name "unconnected-(IC1-RD6-Pad68)") (class "Default")
      (node (ref "IC1") (pin "68") (pinfunction "RD6_68") (pintype "bidirectional"))
    )
    (net (code "118") (name "unconnected-(IC1-RD7-Pad69)") (class "Default")
      (node (ref "IC1") (pin "69") (pinfunction "RD7_69") (pintype "bidirectional"))
    )
    (net (code "119") (name "unconnected-(IC1-RD14-Pad37)") (class "Default")
      (node (ref "IC1") (pin "37") (pinfunction "RD14_37") (pintype "bidirectional"))
    )
    (net (code "120") (name "unconnected-(IC1-RD15-Pad38)") (class "Default")
      (node (ref "IC1") (pin "38") (pinfunction "RD15_38") (pintype "bidirectional"))
    )
    (net (code "121") (name "unconnected-(IC1-RE0-Pad76)") (class "Default")
      (node (ref "IC1") (pin "76") (pinfunction "RE0_76") (pintype "bidirectional"))
    )
    (net (code "122") (name "unconnected-(IC1-RF0-Pad72)") (class "Default")
      (node (ref "IC1") (pin "72") (pinfunction "RF0_72") (pintype "bidirectional"))
    )
    (net (code "123") (name "unconnected-(IC1-RF1-Pad73)") (class "Default")
      (node (ref "IC1") (pin "73") (pinfunction "RF1_73") (pintype "bidirectional"))
    )
    (net (code "124") (name "unconnected-(IC1-RF2-Pad42)") (class "Default")
      (node (ref "IC1") (pin "42") (pinfunction "RF2_42") (pintype "bidirectional"))
    )
    (net (code "125") (name "unconnected-(IC1-RF3-Pad41)") (class "Default")
      (node (ref "IC1") (pin "41") (pinfunction "RF3_41") (pintype "bidirectional"))
    )
    (net (code "126") (name "unconnected-(IC1-RF4-Pad39)") (class "Default")
      (node (ref "IC1") (pin "39") (pinfunction "RF4_39") (pintype "bidirectional"))
    )
    (net (code "127") (name "unconnected-(IC1-RF5-Pad40)") (class "Default")
      (node (ref "IC1") (pin "40") (pinfunction "RF5_40") (pintype "bidirectional"))
    )
    (net (code "128") (name "unconnected-(IC1-RF8-Pad43)") (class "Default")
      (node (ref "IC1") (pin "43") (pinfunction "RF8_43") (pintype "bidirectional"))
    )
    (net (code "129") (name "unconnected-(IC1-RG0-Pad75)") (class "Default")
      (node (ref "IC1") (pin "75") (pinfunction "RG0_75") (pintype "bidirectional"))
    )
    (net (code "130") (name "unconnected-(IC1-RG1-Pad74)") (class "Default")
      (node (ref "IC1") (pin "74") (pinfunction "RG1_74") (pintype "bidirectional"))
    )
    (net (code "131") (name "unconnected-(IC2-ADC-PadP$25)") (class "Default")
      (node (ref "IC2") (pin "P$25") (pinfunction "ADC_P$25") (pintype "bidirectional"))
    )
    (net (code "132") (name "unconnected-(IC2-DISP_CLK-PadP$11)") (class "Default")
      (node (ref "IC2") (pin "P$11") (pinfunction "DISP_CLK_P$11") (pintype "bidirectional"))
    )
    (net (code "133") (name "unconnected-(IC2-DISP_CS-PadP$14)") (class "Default")
      (node (ref "IC2") (pin "P$14") (pinfunction "DISP_CS_P$14") (pintype "bidirectional"))
    )
    (net (code "134") (name "unconnected-(IC2-DISP_DATA-PadP$12)") (class "Default")
      (node (ref "IC2") (pin "P$12") (pinfunction "DISP_DATA_P$12") (pintype "bidirectional"))
    )
    (net (code "135") (name "unconnected-(IC2-DISP_DC-PadP$13)") (class "Default")
      (node (ref "IC2") (pin "P$13") (pinfunction "DISP_DC_P$13") (pintype "bidirectional"))
    )
    (net (code "136") (name "unconnected-(IC2-GPIO1{slash}KBR4-PadP$40)") (class "Default")
      (node (ref "IC2") (pin "P$40") (pinfunction "GPIO1/KBR4_P$40") (pintype "bidirectional"))
    )
    (net (code "137") (name "unconnected-(IC2-GPIO2{slash}KBR3-PadP$41)") (class "Default")
      (node (ref "IC2") (pin "P$41") (pinfunction "GPIO2/KBR3_P$41") (pintype "bidirectional"))
    )
    (net (code "138") (name "unconnected-(IC2-GPIO3{slash}KBR2-PadP$42)") (class "Default")
      (node (ref "IC2") (pin "P$42") (pinfunction "GPIO3/KBR2_P$42") (pintype "bidirectional"))
    )
    (net (code "139") (name "unconnected-(IC2-GPIO4{slash}KBR1-PadP$43)") (class "Default")
      (node (ref "IC2") (pin "P$43") (pinfunction "GPIO4/KBR1_P$43") (pintype "bidirectional"))
    )
    (net (code "140") (name "unconnected-(IC2-GPIO5{slash}KBR0-PadP$44)") (class "Default")
      (node (ref "IC2") (pin "P$44") (pinfunction "GPIO5/KBR0_P$44") (pintype "bidirectional"))
    )
    (net (code "141") (name "unconnected-(IC2-GPIO6{slash}KBC4-PadP$47)") (class "Default")
      (node (ref "IC2") (pin "P$47") (pinfunction "GPIO6/KBC4_P$47") (pintype "bidirectional"))
    )
    (net (code "142") (name "unconnected-(IC2-GPIO7{slash}KBC3-PadP$48)") (class "Default")
      (node (ref "IC2") (pin "P$48") (pinfunction "GPIO7/KBC3_P$48") (pintype "bidirectional"))
    )
    (net (code "143") (name "unconnected-(IC2-GPIO8{slash}KBC2-PadP$49)") (class "Default")
      (node (ref "IC2") (pin "P$49") (pinfunction "GPIO8/KBC2_P$49") (pintype "bidirectional"))
    )
    (net (code "144") (name "unconnected-(IC2-GPIO9{slash}KBC1-PadP$50)") (class "Default")
      (node (ref "IC2") (pin "P$50") (pinfunction "GPIO9/KBC1_P$50") (pintype "bidirectional"))
    )
    (net (code "145") (name "unconnected-(IC2-GPIO10-PadP$51)") (class "Default")
      (node (ref "IC2") (pin "P$51") (pinfunction "GPIO10_P$51") (pintype "bidirectional"))
    )
    (net (code "146") (name "unconnected-(IC2-LINEIN_L-PadP$24)") (class "Default")
      (node (ref "IC2") (pin "P$24") (pinfunction "LINEIN_L_P$24") (pintype "bidirectional"))
    )
    (net (code "147") (name "unconnected-(IC2-LINEIN_R-PadP$23)") (class "Default")
      (node (ref "IC2") (pin "P$23") (pinfunction "LINEIN_R_P$23") (pintype "bidirectional"))
    )
    (net (code "148") (name "unconnected-(IC2-MIC_N-PadP$20)") (class "Default")
      (node (ref "IC2") (pin "P$20") (pinfunction "MIC_N_P$20") (pintype "bidirectional"))
    )
    (net (code "149") (name "unconnected-(IC2-MIC_P-PadP$19)") (class "Default")
      (node (ref "IC2") (pin "P$19") (pinfunction "MIC_P_P$19") (pintype "bidirectional"))
    )
    (net (code "150") (name "unconnected-(IC2-NC1-PadP$2)") (class "Default")
      (node (ref "IC2") (pin "P$2") (pinfunction "NC1_P$2") (pintype "no_connect"))
    )
    (net (code "151") (name "unconnected-(IC2-NC2-PadP$6)") (class "Default")
      (node (ref "IC2") (pin "P$6") (pinfunction "NC2_P$6") (pintype "no_connect"))
    )
    (net (code "152") (name "unconnected-(IC2-PWM1-PadP$35)") (class "Default")
      (node (ref "IC2") (pin "P$35") (pinfunction "PWM1_P$35") (pintype "bidirectional"))
    )
    (net (code "153") (name "unconnected-(IC2-PWM2-PadP$36)") (class "Default")
      (node (ref "IC2") (pin "P$36") (pinfunction "PWM2_P$36") (pintype "bidirectional"))
    )
    (net (code "154") (name "unconnected-(IC2-SCL-PadP$38)") (class "Default")
      (node (ref "IC2") (pin "P$38") (pinfunction "SCL_P$38") (pintype "bidirectional"))
    )
    (net (code "155") (name "unconnected-(IC2-SDA-PadP$37)") (class "Default")
      (node (ref "IC2") (pin "P$37") (pinfunction "SDA_P$37") (pintype "bidirectional"))
    )
    (net (code "156") (name "unconnected-(IC2-SIM_PRESENCE-PadP$34)") (class "Default")
      (node (ref "IC2") (pin "P$34") (pinfunction "SIM_PRESENCE_P$34") (pintype "bidirectional"))
    )
    (net (code "157") (name "unconnected-(IC2-SPK_N-PadP$22)") (class "Default")
      (node (ref "IC2") (pin "P$22") (pinfunction "SPK_N_P$22") (pintype "bidirectional"))
    )
    (net (code "158") (name "unconnected-(IC2-SPK_P-PadP$21)") (class "Default")
      (node (ref "IC2") (pin "P$21") (pinfunction "SPK_P_P$21") (pintype "bidirectional"))
    )
    (net (code "159") (name "unconnected-(J2-Pad6)") (class "Default")
      (node (ref "J2") (pin "6") (pinfunction "6_6") (pintype "passive"))
    )
    (net (code "160") (name "unconnected-(SLOT1-DAT1-PadT8)") (class "Default")
      (node (ref "SLOT1") (pin "T8") (pinfunction "DAT1_T8") (pintype "bidirectional"))
    )
    (net (code "161") (name "unconnected-(SLOT1-DAT2-PadT1)") (class "Default")
      (node (ref "SLOT1") (pin "T1") (pinfunction "DAT2_T1") (pintype "bidirectional"))
    )
    (net (code "162") (name "unconnected-(SLOT1-PadST1)") (class "Default")
      (node (ref "SLOT1") (pin "ST1") (pinfunction "ST1_ST1") (pintype "bidirectional"))
    )
    (net (code "163") (name "unconnected-(SLOT1-PadST2)") (class "Default")
      (node (ref "SLOT1") (pin "ST2") (pinfunction "ST2_ST2") (pintype "bidirectional"))
    )
    (net (code "164") (name "unconnected-(SLOT1-SHIELD1-PadG1)") (class "Default")
      (node (ref "SLOT1") (pin "G1") (pinfunction "SHIELD1_G1") (pintype "bidirectional"))
    )
    (net (code "165") (name "unconnected-(SLOT1-SHIELD2-PadG2)") (class "Default")
      (node (ref "SLOT1") (pin "G2") (pinfunction "SHIELD2_G2") (pintype "bidirectional"))
    )
    (net (code "166") (name "unconnected-(SLOT1-SHIELD3-PadG3)") (class "Default")
      (node (ref "SLOT1") (pin "G3") (pinfunction "SHIELD3_G3") (pintype "bidirectional"))
    )
    (net (code "167") (name "unconnected-(SLOT1-SIM_VPP-PadS5)") (class "Default")
      (node (ref "SLOT1") (pin "S5") (pinfunction "SIM_VPP_S5") (pintype "bidirectional"))
    )
    (net (code "168") (name "unconnected-(U1-NC^(1)-Pad7)") (class "Default")
      (node (ref "U1") (pin "7") (pinfunction "NC^(1)_7") (pintype "no_connect"))
    )
    (net (code "169") (name "unconnected-(U1-NC^(1)_2-Pad1)") (class "Default")
      (node (ref "U1") (pin "1") (pinfunction "NC^(1)_2_1") (pintype "no_connect"))
    )
    (net (code "170") (name "unconnected-(U2-NC^(1)-Pad7)") (class "Default")
      (node (ref "U2") (pin "7") (pinfunction "NC^(1)_7") (pintype "no_connect"))
    )
    (net (code "171") (name "unconnected-(U2-NC^(1)_2-Pad1)") (class "Default")
      (node (ref "U2") (pin "1") (pinfunction "NC^(1)_2_1") (pintype "no_connect"))
    )
    (net (code "172") (name "unconnected-(U4-NC^(1)-Pad7)") (class "Default")
      (node (ref "U4") (pin "7") (pinfunction "NC^(1)_7") (pintype "no_connect"))
    )
    (net (code "173") (name "unconnected-(U4-NC^(1)_2-Pad1)") (class "Default")
      (node (ref "U4") (pin "1") (pinfunction "NC^(1)_2_1") (pintype "no_connect"))
    )
    (net (code "174") (name "unconnected-(U7-Pad3)") (class "Default")
      (node (ref "U7") (pin "3") (pinfunction "3_3") (pintype "bidirectional"))
    )
    (net (code "175") (name "unconnected-(U11-NC_3-Pad3)") (class "Default")
      (node (ref "U11") (pin "3") (pinfunction "NC_3_3") (pintype "no_connect"))
    )
    (net (code "176") (name "unconnected-(U11-NC_8-Pad8)") (class "Default")
      (node (ref "U11") (pin "8") (pinfunction "NC_8_8") (pintype "no_connect"))
    )
    (net (code "177") (name "unconnected-(U11-NC_13-Pad13)") (class "Default")
      (node (ref "U11") (pin "13") (pinfunction "NC_13_13") (pintype "no_connect"))
    )
    (net (code "178") (name "unconnected-(U11-NC_16-Pad16)") (class "Default")
      (node (ref "U11") (pin "16") (pinfunction "NC_16_16") (pintype "no_connect"))
    )
    (net (code "179") (name "unconnected-(USB1-ID-Pad4)") (class "Default")
      (node (ref "USB1") (pin "4") (pinfunction "ID_4") (pintype "bidirectional"))
    )
  )
)
